# BLL-EBOOK-3506.net
KiCad netlist of a schematic drawn in EAGLE
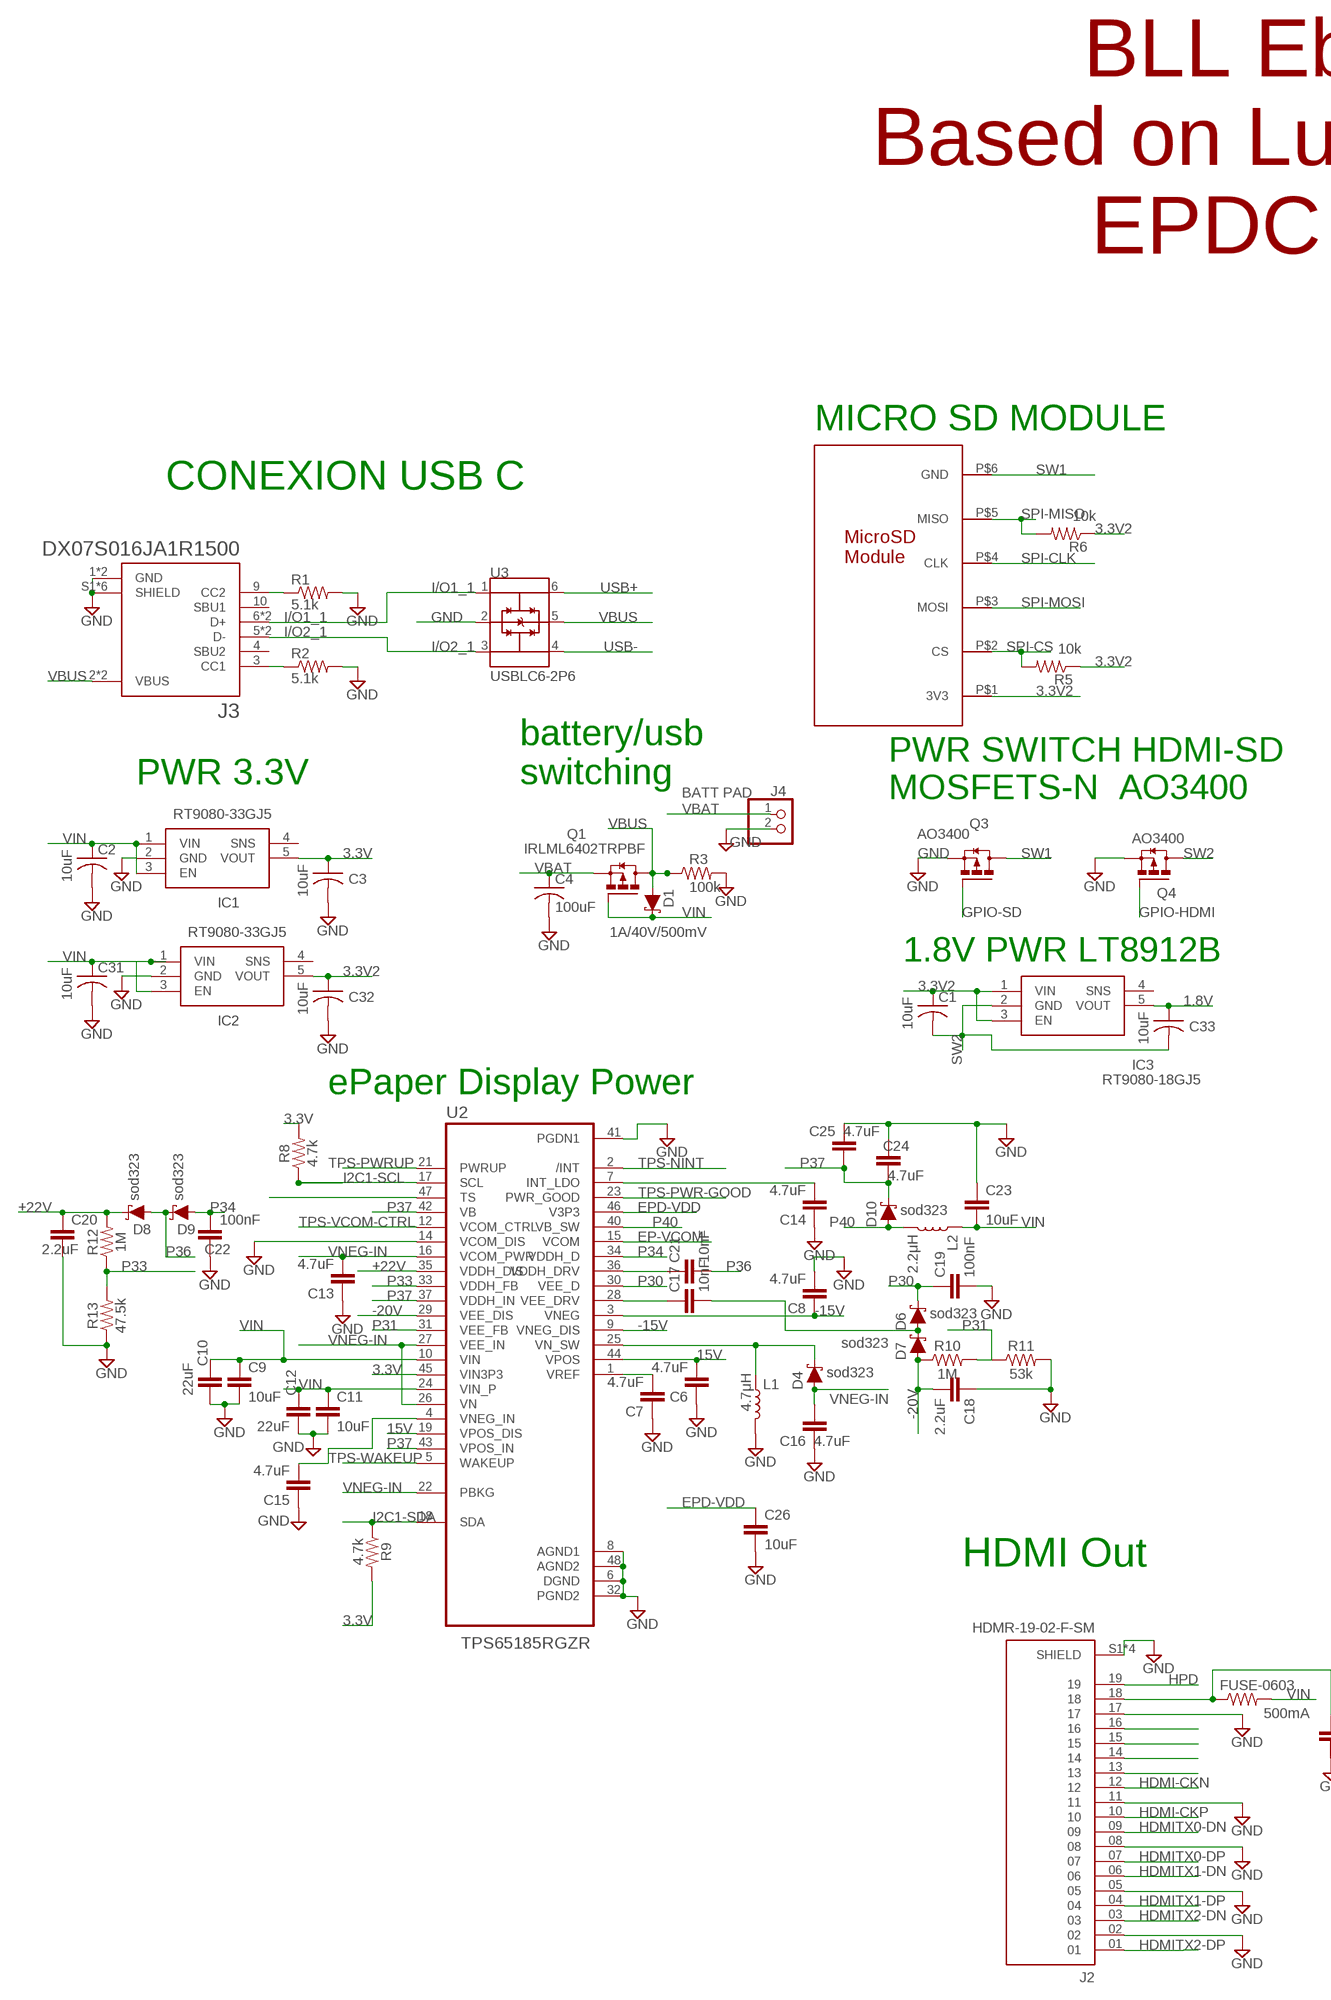
[diagram p0: schematic, sheet 1, part 1 of 2]
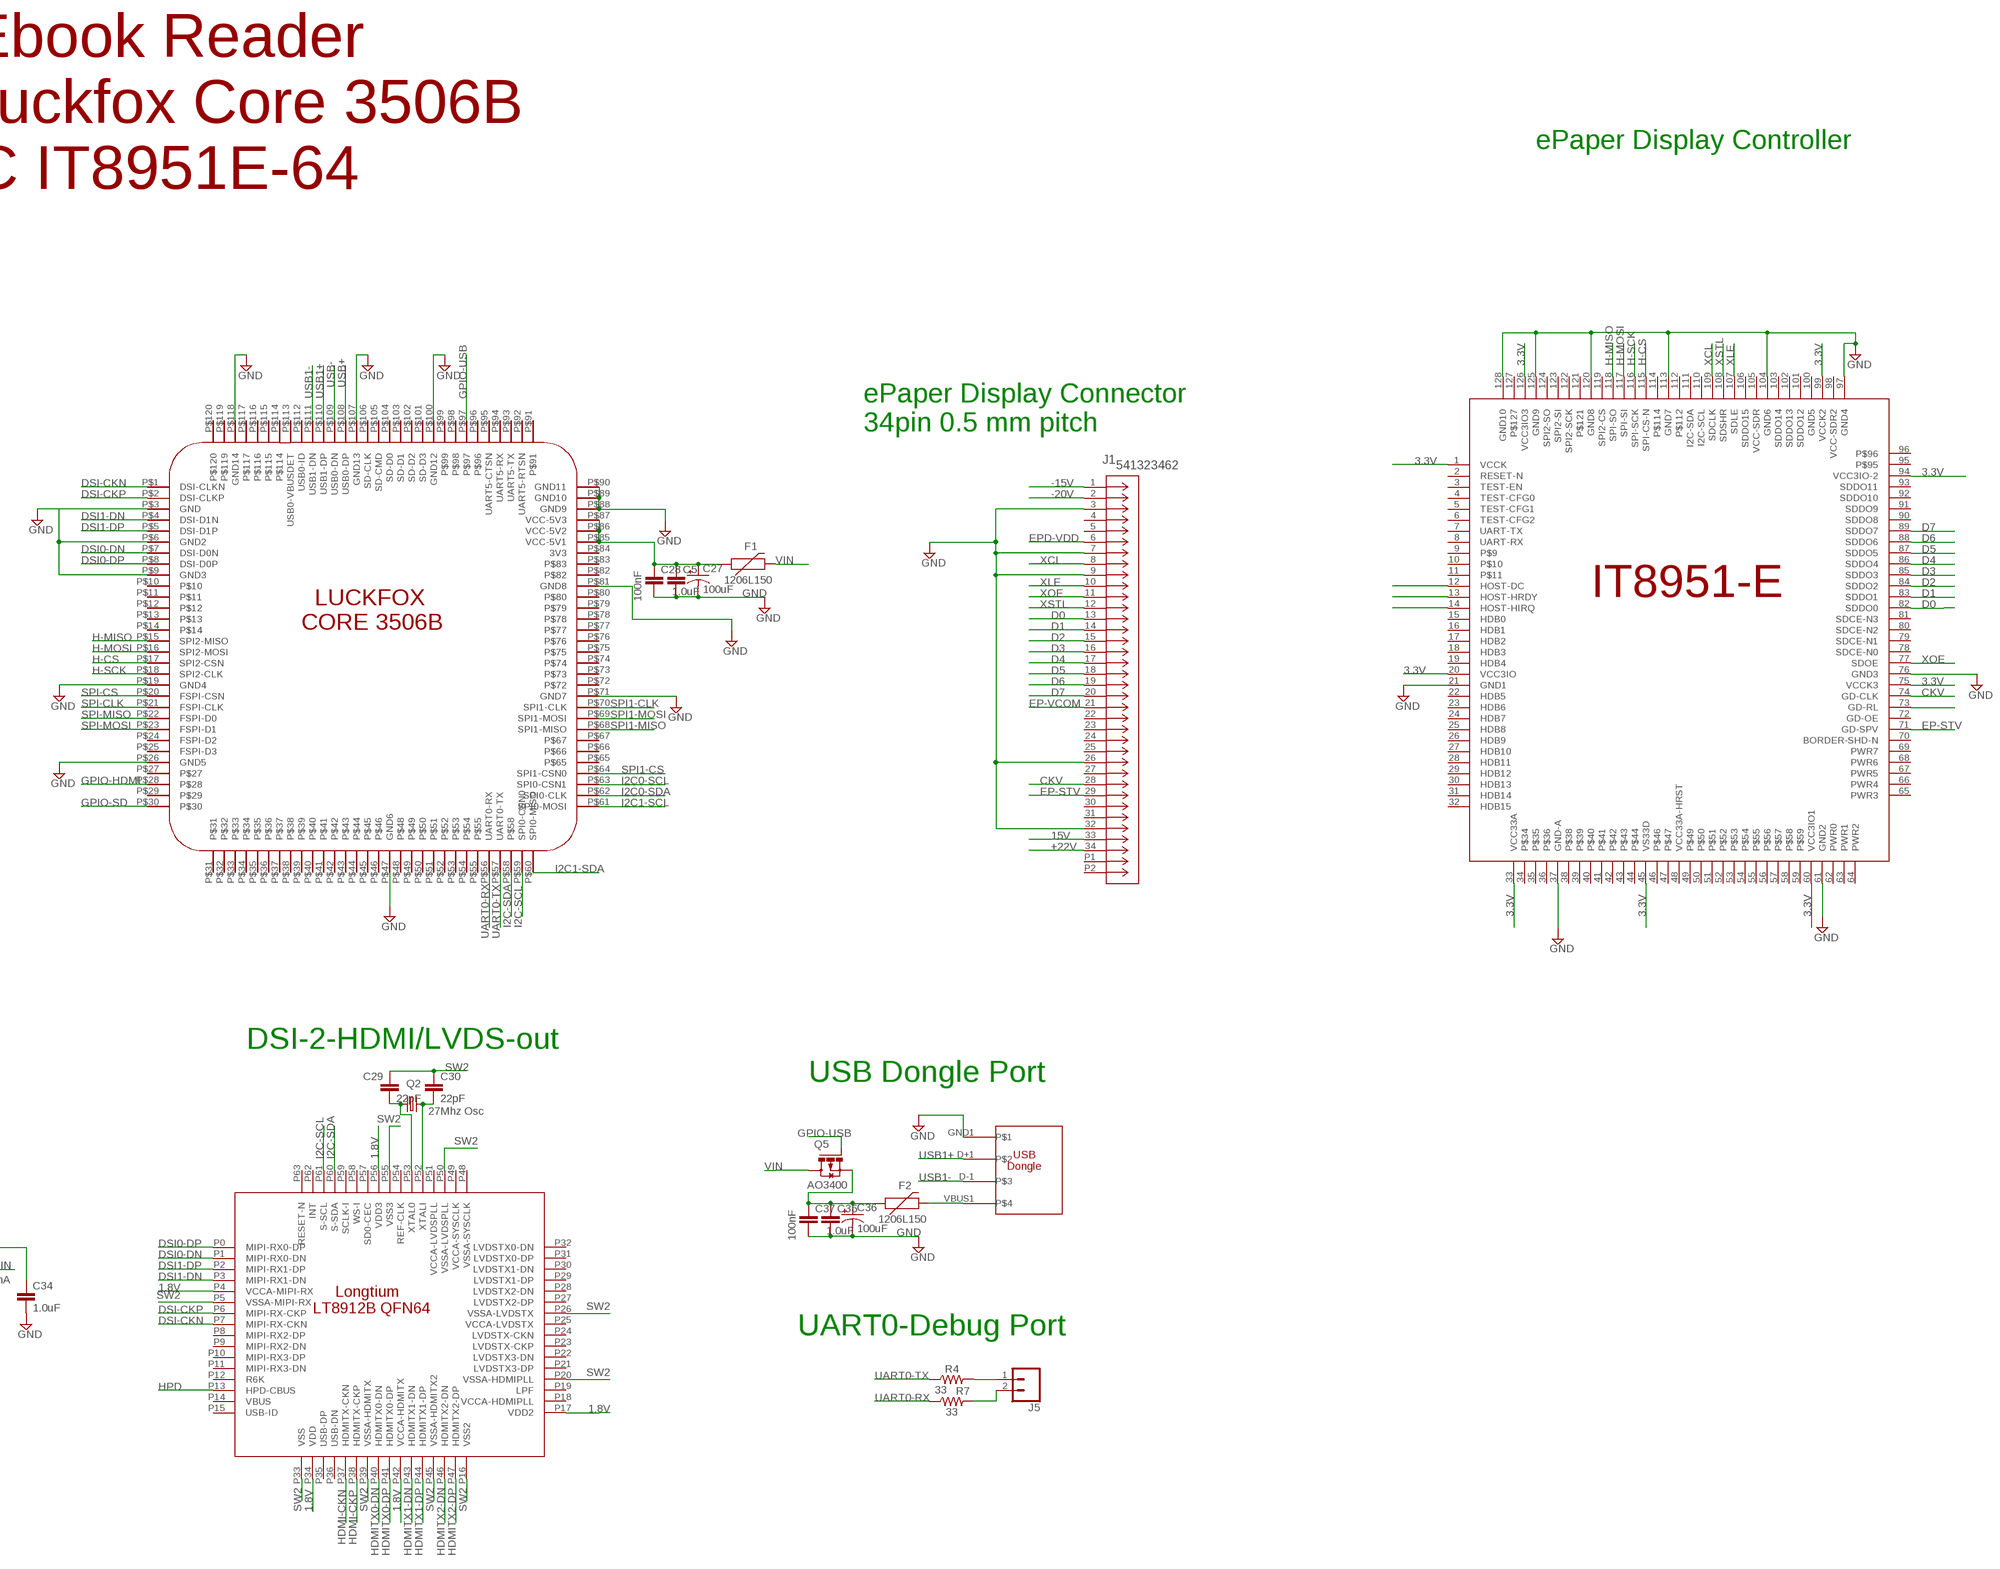
[diagram p1: schematic, sheet 1, part 2 of 2]

(export (version "E")
  (design (tool "Eeschema 10.0.6"))
  (components
    (comp (ref "C1")
      (value "10uF")
      (footprint "eagle-import:C0603")
      (libsource (lib "eagle-import") (part "C-USC0603"))
    )
    (comp (ref "C2")
      (value "10uF")
      (footprint "eagle-import:C0603")
      (libsource (lib "eagle-import") (part "C-USC0603"))
    )
    (comp (ref "C3")
      (value "10uF")
      (footprint "eagle-import:C0603")
      (libsource (lib "eagle-import") (part "C-USC0603"))
    )
    (comp (ref "C4")
      (value "100uF")
      (footprint "eagle-import:C0603")
      (libsource (lib "eagle-import") (part "C-USC0603"))
    )
    (comp (ref "C5")
      (value "1.0uF")
      (footprint "eagle-import:0603")
      (libsource (lib "eagle-import") (part "1.0UF-0603-16V-10%-X7R"))
    )
    (comp (ref "C6")
      (value "4.7uF")
      (footprint "eagle-import:0603")
      (libsource (lib "eagle-import") (part "4.7UF-0603-35V-(20%)"))
    )
    (comp (ref "C7")
      (value "4.7uF")
      (footprint "eagle-import:0603")
      (libsource (lib "eagle-import") (part "4.7UF-0603-35V-(20%)"))
    )
    (comp (ref "C8")
      (value "4.7uF")
      (footprint "eagle-import:0603")
      (libsource (lib "eagle-import") (part "4.7UF-0603-35V-(20%)"))
    )
    (comp (ref "C9")
      (value "10uF")
      (footprint "eagle-import:0805")
      (libsource (lib "eagle-import") (part "10UF-0805-10V-10%"))
    )
    (comp (ref "C10")
      (value "22uF")
      (footprint "eagle-import:0805")
      (libsource (lib "eagle-import") (part "22UF-0805-16V-20%"))
    )
    (comp (ref "C11")
      (value "10uF")
      (footprint "eagle-import:0805")
      (libsource (lib "eagle-import") (part "10UF-0805-10V-10%"))
    )
    (comp (ref "C12")
      (value "22uF")
      (footprint "eagle-import:0805")
      (libsource (lib "eagle-import") (part "22UF-0805-16V-20%"))
    )
    (comp (ref "C13")
      (value "4.7uF")
      (footprint "eagle-import:0603")
      (libsource (lib "eagle-import") (part "4.7UF-0603-35V-(20%)"))
    )
    (comp (ref "C14")
      (value "4.7uF")
      (footprint "eagle-import:0603")
      (libsource (lib "eagle-import") (part "4.7UF-0603-35V-(20%)"))
    )
    (comp (ref "C15")
      (value "4.7uF")
      (footprint "eagle-import:0603")
      (libsource (lib "eagle-import") (part "4.7UF-0603-35V-(20%)"))
    )
    (comp (ref "C16")
      (value "4.7uF")
      (footprint "eagle-import:0603")
      (libsource (lib "eagle-import") (part "4.7UF-0603-35V-(20%)"))
    )
    (comp (ref "C17")
      (value "10nF")
      (footprint "eagle-import:0603")
      (libsource (lib "eagle-import") (part "10NF-0603-50V-10%"))
    )
    (comp (ref "C18")
      (value "2.2uF")
      (footprint "eagle-import:1206")
      (libsource (lib "eagle-import") (part "2.2UF-1206-50V-10%"))
    )
    (comp (ref "C19")
      (value "100nF")
      (footprint "eagle-import:0603")
      (libsource (lib "eagle-import") (part "DNP-0603"))
    )
    (comp (ref "C20")
      (value "2.2uF")
      (footprint "eagle-import:1206")
      (libsource (lib "eagle-import") (part "2.2UF-1206-50V-10%"))
    )
    (comp (ref "C21")
      (value "10nF")
      (footprint "eagle-import:0603")
      (libsource (lib "eagle-import") (part "10NF-0603-50V-10%"))
    )
    (comp (ref "C22")
      (value "100nF")
      (footprint "eagle-import:0603")
      (libsource (lib "eagle-import") (part "DNP-0603"))
    )
    (comp (ref "C23")
      (value "10uF")
      (footprint "eagle-import:0805")
      (libsource (lib "eagle-import") (part "10UF-0805-10V-10%"))
    )
    (comp (ref "C24")
      (value "4.7uF")
      (footprint "eagle-import:0603")
      (libsource (lib "eagle-import") (part "4.7UF-0603-35V-(20%)"))
    )
    (comp (ref "C25")
      (value "4.7uF")
      (footprint "eagle-import:0603")
      (libsource (lib "eagle-import") (part "4.7UF-0603-35V-(20%)"))
    )
    (comp (ref "C26")
      (value "10uF")
      (footprint "eagle-import:0805")
      (libsource (lib "eagle-import") (part "10UF-0805-10V-10%"))
    )
    (comp (ref "C27")
      (value "100uF")
      (footprint "eagle-import:EIA3528")
      (libsource (lib "eagle-import") (part "100UF-POLAR-EIA3528-10V-20%(TANT)"))
    )
    (comp (ref "C28")
      (value "100nF")
      (footprint "eagle-import:0805")
      (libsource (lib "eagle-import") (part "CAP-0805"))
    )
    (comp (ref "C29")
      (value "22pF")
      (footprint "eagle-import:0603")
      (libsource (lib "eagle-import") (part "22PF-0603-50V-5%"))
    )
    (comp (ref "C30")
      (value "22pF")
      (footprint "eagle-import:0603")
      (libsource (lib "eagle-import") (part "22PF-0603-50V-5%"))
    )
    (comp (ref "C31")
      (value "10uF")
      (footprint "eagle-import:C0603")
      (libsource (lib "eagle-import") (part "C-USC0603"))
    )
    (comp (ref "C32")
      (value "10uF")
      (footprint "eagle-import:C0603")
      (libsource (lib "eagle-import") (part "C-USC0603"))
    )
    (comp (ref "C33")
      (value "10uF")
      (footprint "eagle-import:C0603")
      (libsource (lib "eagle-import") (part "C-USC0603"))
    )
    (comp (ref "C34")
      (value "1.0uF")
      (footprint "eagle-import:0603")
      (libsource (lib "eagle-import") (part "1.0UF-0603-16V-10%"))
    )
    (comp (ref "C35")
      (value "1.0uF")
      (footprint "eagle-import:0603")
      (libsource (lib "eagle-import") (part "1.0UF-0603-16V-10%-X7R"))
    )
    (comp (ref "C36")
      (value "100uF")
      (footprint "eagle-import:EIA3528")
      (libsource (lib "eagle-import") (part "100UF-POLAR-EIA3528-10V-20%(TANT)"))
    )
    (comp (ref "C37")
      (value "100nF")
      (footprint "eagle-import:0805")
      (libsource (lib "eagle-import") (part "CAP-0805"))
    )
    (comp (ref "D1")
      (value "1A/40V/500mV")
      (footprint "eagle-import:SMA-DIODE")
      (libsource (lib "eagle-import") (part "DIODE-SCHOTTKY-SS14"))
    )
    (comp (ref "D4")
      (value "sod323")
      (footprint "eagle-import:SOD-323")
      (libsource (lib "eagle-import") (part "DIODE-SCHOTTKY-PMEG4005EJ"))
    )
    (comp (ref "D6")
      (value "sod323")
      (footprint "eagle-import:SOD-323")
      (libsource (lib "eagle-import") (part "DIODE-SCHOTTKY-PMEG4005EJ"))
    )
    (comp (ref "D7")
      (value "sod323")
      (footprint "eagle-import:SOD-323")
      (libsource (lib "eagle-import") (part "DIODE-SCHOTTKY-PMEG4005EJ"))
    )
    (comp (ref "D8")
      (value "sod323")
      (footprint "eagle-import:SOD-323")
      (libsource (lib "eagle-import") (part "DIODE-SCHOTTKY-PMEG4005EJ"))
    )
    (comp (ref "D9")
      (value "sod323")
      (footprint "eagle-import:SOD-323")
      (libsource (lib "eagle-import") (part "DIODE-SCHOTTKY-PMEG4005EJ"))
    )
    (comp (ref "D10")
      (value "sod323")
      (footprint "eagle-import:SOD-323")
      (libsource (lib "eagle-import") (part "DIODE-SCHOTTKY-PMEG4005EJ"))
    )
    (comp (ref "F1")
      (value "1206L150")
      (footprint "eagle-import:1206")
      (libsource (lib "eagle-import") (part "PPTC_6V500MA-2"))
    )
    (comp (ref "F2")
      (value "1206L150")
      (footprint "eagle-import:1206")
      (libsource (lib "eagle-import") (part "PPTC_6V500MA-2"))
    )
    (comp (ref "FUSE-0603")
      (value "500mA")
      (footprint "eagle-import:0603")
      (libsource (lib "eagle-import") (part "1.8MOHM"))
    )
    (comp (ref "IC1")
      (value "RT9080-33GJ5")
      (footprint "eagle-import:SOT94P280X100-5N")
      (fields (field (name "MF") "Richtek USA"))
      (libsource (lib "eagle-import") (part "RT9080-33GJ5"))
    )
    (comp (ref "IC2")
      (value "RT9080-33GJ5")
      (footprint "eagle-import:SOT94P280X100-5N")
      (fields (field (name "MF") "Richtek USA"))
      (libsource (lib "eagle-import") (part "RT9080-33GJ5"))
    )
    (comp (ref "IC3")
      (value "RT9080-18GJ5")
      (footprint "eagle-import:SOT94P280X100-5N")
      (fields (field (name "MF") "Richtek USA") (field (name "MP") "RT9080-33GJ5"))
      (libsource (lib "eagle-import") (part "RT9080-33GJ5"))
    )
    (comp (ref "J1")
      (value "541323462")
      (footprint "eagle-import:CON_541323462_MOL")
      (fields (field (name "MF") "Molex"))
      (libsource (lib "eagle-import") (part "541323462"))
    )
    (comp (ref "J2")
      (value "HDMR-19-02-F-SM")
      (footprint "eagle-import:SAMTEC_HDMR-19-02-F-SM")
      (fields (field (name "MF") "Samtec") (field (name "MP") "HDMR-19-02-F-SM-TR"))
      (libsource (lib "eagle-import") (part "HDMR-19-02-F-SM"))
    )
    (comp (ref "J3")
      (value "DX07S016JA1R1500")
      (footprint "eagle-import:JAE_DX07S016JA1R1500")
      (fields (field (name "MF") "JAE Electronics"))
      (libsource (lib "eagle-import") (part "DX07S016JA1R1500"))
    )
    (comp (ref "J4")
      (value "BATT PAD")
      (footprint "eagle-import:1X02_90")
      (libsource (lib "eagle-import") (part "PINHD-1X2/90"))
    )
    (comp (ref "J5")
      (value "CONN_02LOCK")
      (footprint "eagle-import:1X02_LOCK")
      (libsource (lib "eagle-import") (part "CONN_02LOCK"))
    )
    (comp (ref "L1")
      (value "4.7μH")
      (footprint "eagle-import:1008(2520)")
      (libsource (lib "eagle-import") (part "4.7μH_SHIELDED_INDUCTOR"))
    )
    (comp (ref "L2")
      (value "2.2μH")
      (footprint "eagle-import:0806")
      (libsource (lib "eagle-import") (part "2.2μH_SHIELDED_INDUCTOR"))
    )
    (comp (ref "LT8912")
      (value "LT8912B")
      (footprint "eagle-import:LT8912B")
      (libsource (lib "eagle-import") (part "LT8912B"))
    )
    (comp (ref "Q1")
      (value "IRLML6402TRPBF")
      (footprint "eagle-import:SOT23")
      (fields (field (name "MF") "Infineon Technologies") (field (name "MP") "IRLML6402"))
      (libsource (lib "eagle-import") (part "IRLML6402TRPBF"))
    )
    (comp (ref "Q2")
      (value "27Mhz Osc")
      (footprint "eagle-import:5.0X3.2_2")
      (libsource (lib "eagle-import") (part "KX-9B"))
    )
    (comp (ref "Q3")
      (value "AO3400")
      (footprint "eagle-import:SOT23")
      (fields (field (name "MF") "Infineon Technologies") (field (name "MP") "IRLML6402"))
      (libsource (lib "eagle-import") (part "IRLML6402TRPBF"))
    )
    (comp (ref "Q4")
      (value "AO3400")
      (footprint "eagle-import:SOT23")
      (fields (field (name "MF") "Infineon Technologies") (field (name "MP") "IRLML6402"))
      (libsource (lib "eagle-import") (part "IRLML6402TRPBF"))
    )
    (comp (ref "Q5")
      (value "AO3400")
      (footprint "eagle-import:SOT23")
      (fields (field (name "MF") "Infineon Technologies") (field (name "MP") "IRLML6402"))
      (libsource (lib "eagle-import") (part "IRLML6402TRPBF"))
    )
    (comp (ref "R1")
      (value "5.1k")
      (footprint "eagle-import:M0805")
      (libsource (lib "eagle-import") (part "R-US_M0805"))
    )
    (comp (ref "R2")
      (value "5.1k")
      (footprint "eagle-import:M0805")
      (libsource (lib "eagle-import") (part "R-US_M0805"))
    )
    (comp (ref "R3")
      (value "100k")
      (footprint "eagle-import:R0603")
      (libsource (lib "eagle-import") (part "R-US_R0603"))
    )
    (comp (ref "R4")
      (value "33")
      (footprint "eagle-import:0603")
      (libsource (lib "eagle-import") (part "33OHM-0603-1/10W-1%"))
    )
    (comp (ref "R5")
      (value "10k")
      (footprint "eagle-import:M0805")
      (libsource (lib "eagle-import") (part "R-US_M0805"))
    )
    (comp (ref "R6")
      (value "10k")
      (footprint "eagle-import:M0805")
      (libsource (lib "eagle-import") (part "R-US_M0805"))
    )
    (comp (ref "R7")
      (value "33")
      (footprint "eagle-import:0603")
      (libsource (lib "eagle-import") (part "33OHM-0603-1/10W-1%"))
    )
    (comp (ref "R8")
      (value "4.7k")
      (footprint "eagle-import:0603")
      (libsource (lib "eagle-import") (part "4.7KOHM-0603-1/10W-1%"))
    )
    (comp (ref "R9")
      (value "4.7k")
      (footprint "eagle-import:0603")
      (libsource (lib "eagle-import") (part "4.7KOHM-0603-1/10W-1%"))
    )
    (comp (ref "R10")
      (value "1M")
      (footprint "eagle-import:0603")
      (libsource (lib "eagle-import") (part "1MOHM-0603-1/4W-5%"))
    )
    (comp (ref "R11")
      (value "53k")
      (footprint "eagle-import:0805")
      (libsource (lib "eagle-import") (part "RESISTOR0805"))
    )
    (comp (ref "R12")
      (value "1M")
      (footprint "eagle-import:0603")
      (libsource (lib "eagle-import") (part "1MOHM-0603-1/4W-5%"))
    )
    (comp (ref "R13")
      (value "47.5k")
      (footprint "eagle-import:0805")
      (libsource (lib "eagle-import") (part "RESISTOR0805"))
    )
    (comp (ref "U$1")
      (value "IT8951")
      (footprint "eagle-import:LQFP128_STM")
      (libsource (lib "eagle-import") (part "IT8951"))
    )
    (comp (ref "U$3")
      (value "LUCKFOX_CORE3506")
      (footprint "eagle-import:CORE3506")
      (libsource (lib "eagle-import") (part "LUCKFOX_CORE3506"))
    )
    (comp (ref "U$4")
      (value "MICROSD-MODULE")
      (footprint "eagle-import:MICROSD-MOD")
      (libsource (lib "eagle-import") (part "MICROSD-MODULE"))
    )
    (comp (ref "U$5")
      (value "USB-WIFI-DONGLE")
      (footprint "eagle-import:USB-A-SMT-MALE")
      (libsource (lib "eagle-import") (part "USB-WIFI-DONGLE"))
    )
    (comp (ref "U2")
      (value "TPS65185RGZR")
      (footprint "eagle-import:QFN50P700X700X100-49N")
      (fields (field (name "MF") "Texas Instruments"))
      (libsource (lib "eagle-import") (part "TPS65185RGZR"))
    )
    (comp (ref "U3")
      (value "USBLC6-2P6")
      (footprint "eagle-import:SOT50P160X60-6N")
      (fields (field (name "MF") "STMicroelectronics"))
      (libsource (lib "eagle-import") (part "USBLC6-2P6"))
    )
  )
  (nets
    (net (code "1") (name "/+22V") (class "Default")
      (node (ref "C20") (pin "1") (pinfunction "1_1") (pintype "passive"))
      (node (ref "D8") (pin "C") (pinfunction "C_C") (pintype "passive"))
      (node (ref "J1") (pin "34") (pinfunction "34_34") (pintype "passive"))
      (node (ref "R12") (pin "2") (pinfunction "2_2") (pintype "passive"))
      (node (ref "U2") (pin "35") (pinfunction "VDDH_DIS_35") (pintype "input"))
    )
    (net (code "2") (name "/-15V") (class "Default")
      (node (ref "C8") (pin "1") (pinfunction "1_1") (pintype "passive"))
      (node (ref "J1") (pin "1") (pinfunction "1_1") (pintype "passive"))
      (node (ref "U2") (pin "3") (pinfunction "VNEG_3") (pintype "output"))
      (node (ref "U2") (pin "9") (pinfunction "VNEG_DIS_9") (pintype "output"))
    )
    (net (code "3") (name "/-20V") (class "Default")
      (node (ref "C18") (pin "2") (pinfunction "2_2") (pintype "passive"))
      (node (ref "D7") (pin "A") (pinfunction "A_A") (pintype "passive"))
      (node (ref "J1") (pin "2") (pinfunction "2_2") (pintype "passive"))
      (node (ref "R10") (pin "1") (pinfunction "1_1") (pintype "passive"))
      (node (ref "U2") (pin "29") (pinfunction "VEE_DIS_29") (pintype "input"))
    )
    (net (code "4") (name "/1.8V") (class "Default")
      (node (ref "C33") (pin "1") (pinfunction "1_1") (pintype "passive"))
      (node (ref "IC3") (pin "5") (pinfunction "VOUT_5") (pintype "bidirectional"))
      (node (ref "LT8912") (pin "P17") (pinfunction "VDD2_P17") (pintype "bidirectional"))
      (node (ref "LT8912") (pin "P34") (pinfunction "VDD_P34") (pintype "bidirectional"))
      (node (ref "LT8912") (pin "P4") (pinfunction "VCCA-MIPI-RX_P4") (pintype "bidirectional"))
      (node (ref "LT8912") (pin "P42") (pinfunction "VCCA-HDMITX_P42") (pintype "bidirectional"))
      (node (ref "LT8912") (pin "P56") (pinfunction "VDD3_P56") (pintype "bidirectional"))
    )
    (net (code "5") (name "/3.3V") (class "Default")
      (node (ref "C3") (pin "1") (pinfunction "1_1") (pintype "passive"))
      (node (ref "IC1") (pin "5") (pinfunction "VOUT_5") (pintype "bidirectional"))
      (node (ref "R8") (pin "2") (pinfunction "2_2") (pintype "passive"))
      (node (ref "R9") (pin "2") (pinfunction "2_2") (pintype "passive"))
      (node (ref "U$1") (pin "1") (pinfunction "VCCK_1") (pintype "bidirectional"))
      (node (ref "U$1") (pin "126") (pinfunction "VCC3IO3_126") (pintype "bidirectional"))
      (node (ref "U$1") (pin "20") (pinfunction "VCC3IO_20") (pintype "bidirectional"))
      (node (ref "U$1") (pin "33") (pinfunction "VCC33A_33") (pintype "bidirectional"))
      (node (ref "U$1") (pin "45") (pinfunction "VS33D_45") (pintype "bidirectional"))
      (node (ref "U$1") (pin "60") (pinfunction "VCC3IO1_60") (pintype "bidirectional"))
      (node (ref "U$1") (pin "75") (pinfunction "VCCK3_75") (pintype "bidirectional"))
      (node (ref "U$1") (pin "94") (pinfunction "VCC3IO-2_94") (pintype "bidirectional"))
      (node (ref "U$1") (pin "99") (pinfunction "VCCK2_99") (pintype "bidirectional"))
      (node (ref "U2") (pin "45") (pinfunction "VIN3P3_45") (pintype "input"))
    )
    (net (code "6") (name "/3.3V2") (class "Default")
      (node (ref "C1") (pin "1") (pinfunction "1_1") (pintype "passive"))
      (node (ref "C32") (pin "1") (pinfunction "1_1") (pintype "passive"))
      (node (ref "IC2") (pin "5") (pinfunction "VOUT_5") (pintype "bidirectional"))
      (node (ref "IC3") (pin "1") (pinfunction "VIN_1") (pintype "bidirectional"))
      (node (ref "IC3") (pin "3") (pinfunction "EN_3") (pintype "bidirectional"))
      (node (ref "R5") (pin "1") (pinfunction "1_1") (pintype "passive"))
      (node (ref "R6") (pin "1") (pinfunction "1_1") (pintype "passive"))
      (node (ref "U$4") (pin "P$1") (pinfunction "3V3_P$1") (pintype "bidirectional"))
    )
    (net (code "7") (name "/15V") (class "Default")
      (node (ref "C6") (pin "2") (pinfunction "2_2") (pintype "passive"))
      (node (ref "J1") (pin "33") (pinfunction "33_33") (pintype "passive"))
      (node (ref "U2") (pin "19") (pinfunction "VPOS_DIS_19") (pintype "input"))
      (node (ref "U2") (pin "44") (pinfunction "VPOS_44") (pintype "output"))
    )
    (net (code "8") (name "/CKV") (class "Default")
      (node (ref "J1") (pin "28") (pinfunction "28_28") (pintype "passive"))
      (node (ref "U$1") (pin "74") (pinfunction "GD-CLK_74") (pintype "bidirectional"))
    )
    (net (code "9") (name "/D0") (class "Default")
      (node (ref "J1") (pin "13") (pinfunction "13_13") (pintype "passive"))
      (node (ref "U$1") (pin "82") (pinfunction "SDDO0_82") (pintype "bidirectional"))
    )
    (net (code "10") (name "/D1") (class "Default")
      (node (ref "J1") (pin "14") (pinfunction "14_14") (pintype "passive"))
      (node (ref "U$1") (pin "83") (pinfunction "SDDO1_83") (pintype "bidirectional"))
    )
    (net (code "11") (name "/D2") (class "Default")
      (node (ref "J1") (pin "15") (pinfunction "15_15") (pintype "passive"))
      (node (ref "U$1") (pin "84") (pinfunction "SDDO2_84") (pintype "bidirectional"))
    )
    (net (code "12") (name "/D3") (class "Default")
      (node (ref "J1") (pin "16") (pinfunction "16_16") (pintype "passive"))
      (node (ref "U$1") (pin "85") (pinfunction "SDDO3_85") (pintype "bidirectional"))
    )
    (net (code "13") (name "/D4") (class "Default")
      (node (ref "J1") (pin "17") (pinfunction "17_17") (pintype "passive"))
      (node (ref "U$1") (pin "86") (pinfunction "SDDO4_86") (pintype "bidirectional"))
    )
    (net (code "14") (name "/D5") (class "Default")
      (node (ref "J1") (pin "18") (pinfunction "18_18") (pintype "passive"))
      (node (ref "U$1") (pin "87") (pinfunction "SDDO5_87") (pintype "bidirectional"))
    )
    (net (code "15") (name "/D6") (class "Default")
      (node (ref "J1") (pin "19") (pinfunction "19_19") (pintype "passive"))
      (node (ref "U$1") (pin "88") (pinfunction "SDDO6_88") (pintype "bidirectional"))
    )
    (net (code "16") (name "/D7") (class "Default")
      (node (ref "J1") (pin "20") (pinfunction "20_20") (pintype "passive"))
      (node (ref "U$1") (pin "89") (pinfunction "SDDO7_89") (pintype "bidirectional"))
    )
    (net (code "17") (name "/DSI-CKN") (class "Default")
      (node (ref "LT8912") (pin "P7") (pinfunction "MIPI-RX-CKN_P7") (pintype "bidirectional"))
      (node (ref "U$3") (pin "P$1") (pinfunction "DSI-CLKN_P$1") (pintype "output"))
    )
    (net (code "18") (name "/DSI-CKP") (class "Default")
      (node (ref "LT8912") (pin "P6") (pinfunction "MIPI-RX-CKP_P6") (pintype "bidirectional"))
      (node (ref "U$3") (pin "P$2") (pinfunction "DSI-CLKP_P$2") (pintype "bidirectional"))
    )
    (net (code "19") (name "/DSI0-DN") (class "Default")
      (node (ref "LT8912") (pin "P1") (pinfunction "MIPI-RX0-DN_P1") (pintype "bidirectional"))
      (node (ref "U$3") (pin "P$7") (pinfunction "DSI-D0N_P$7") (pintype "bidirectional"))
    )
    (net (code "20") (name "/DSI0-DP") (class "Default")
      (node (ref "LT8912") (pin "P0") (pinfunction "MIPI-RX0-DP_P0") (pintype "bidirectional"))
      (node (ref "U$3") (pin "P$8") (pinfunction "DSI-D0P_P$8") (pintype "bidirectional"))
    )
    (net (code "21") (name "/DSI1-DN") (class "Default")
      (node (ref "LT8912") (pin "P3") (pinfunction "MIPI-RX1-DN_P3") (pintype "bidirectional"))
      (node (ref "U$3") (pin "P$4") (pinfunction "DSI-D1N_P$4") (pintype "bidirectional"))
    )
    (net (code "22") (name "/DSI1-DP") (class "Default")
      (node (ref "LT8912") (pin "P2") (pinfunction "MIPI-RX1-DP_P2") (pintype "bidirectional"))
      (node (ref "U$3") (pin "P$5") (pinfunction "DSI-D1P_P$5") (pintype "bidirectional"))
    )
    (net (code "23") (name "/EP-STV") (class "Default")
      (node (ref "J1") (pin "29") (pinfunction "29_29") (pintype "passive"))
      (node (ref "U$1") (pin "71") (pinfunction "GD-SPV_71") (pintype "bidirectional"))
    )
    (net (code "24") (name "/EP-VCOM") (class "Default")
      (node (ref "J1") (pin "21") (pinfunction "21_21") (pintype "passive"))
      (node (ref "U2") (pin "15") (pinfunction "VCOM_15") (pintype "output"))
    )
    (net (code "25") (name "/EPD-VDD") (class "Default")
      (node (ref "C26") (pin "1") (pinfunction "1_1") (pintype "passive"))
      (node (ref "J1") (pin "6") (pinfunction "6_6") (pintype "passive"))
      (node (ref "U2") (pin "46") (pinfunction "V3P3_46") (pintype "output"))
    )
    (net (code "26") (name "/GPIO-HDMI") (class "Default")
      (node (ref "Q4") (pin "1") (pinfunction "G_1") (pintype "passive"))
      (node (ref "U$3") (pin "P$28") (pinfunction "P$28_P$28") (pintype "bidirectional"))
    )
    (net (code "27") (name "/GPIO-SD") (class "Default")
      (node (ref "Q3") (pin "1") (pinfunction "G_1") (pintype "passive"))
      (node (ref "U$3") (pin "P$30") (pinfunction "P$30_P$30") (pintype "bidirectional"))
    )
    (net (code "28") (name "/GPIO-USB") (class "Default")
      (node (ref "Q5") (pin "1") (pinfunction "G_1") (pintype "passive"))
      (node (ref "U$3") (pin "P$97") (pinfunction "P$97_P$97") (pintype "bidirectional"))
    )
    (net (code "29") (name "/H-CS") (class "Default")
      (node (ref "U$1") (pin "115") (pinfunction "SPI-CS-N_115") (pintype "bidirectional"))
      (node (ref "U$3") (pin "P$17") (pinfunction "SPI2-CSN_P$17") (pintype "bidirectional"))
    )
    (net (code "30") (name "/H-MISO") (class "Default")
      (node (ref "U$1") (pin "118") (pinfunction "SPI-SO_118") (pintype "bidirectional"))
      (node (ref "U$3") (pin "P$15") (pinfunction "SPI2-MISO_P$15") (pintype "bidirectional"))
    )
    (net (code "31") (name "/H-MOSI") (class "Default")
      (node (ref "U$1") (pin "117") (pinfunction "SPI-SI_117") (pintype "bidirectional"))
      (node (ref "U$3") (pin "P$16") (pinfunction "SPI2-MOSI_P$16") (pintype "bidirectional"))
    )
    (net (code "32") (name "/H-SCK") (class "Default")
      (node (ref "U$1") (pin "116") (pinfunction "SPI-SCK_116") (pintype "bidirectional"))
      (node (ref "U$3") (pin "P$18") (pinfunction "SPI2-CLK_P$18") (pintype "bidirectional"))
    )
    (net (code "33") (name "/HDMI-CKN") (class "Default")
      (node (ref "J2") (pin "12") (pinfunction "12_12") (pintype "bidirectional"))
      (node (ref "LT8912") (pin "P37") (pinfunction "HDMITX-CKN_P37") (pintype "bidirectional"))
    )
    (net (code "34") (name "/HDMI-CKP") (class "Default")
      (node (ref "J2") (pin "10") (pinfunction "10_10") (pintype "bidirectional"))
      (node (ref "LT8912") (pin "P38") (pinfunction "HDMITX-CKP_P38") (pintype "bidirectional"))
    )
    (net (code "35") (name "/HDMITX0-DN") (class "Default")
      (node (ref "J2") (pin "09") (pinfunction "09_09") (pintype "bidirectional"))
      (node (ref "LT8912") (pin "P40") (pinfunction "HDMITX0-DN_P40") (pintype "bidirectional"))
    )
    (net (code "36") (name "/HDMITX0-DP") (class "Default")
      (node (ref "J2") (pin "07") (pinfunction "07_07") (pintype "bidirectional"))
      (node (ref "LT8912") (pin "P41") (pinfunction "HDMITX0-DP_P41") (pintype "bidirectional"))
    )
    (net (code "37") (name "/HDMITX1-DN") (class "Default")
      (node (ref "J2") (pin "06") (pinfunction "06_06") (pintype "bidirectional"))
      (node (ref "LT8912") (pin "P43") (pinfunction "HDMITX1-DN_P43") (pintype "bidirectional"))
    )
    (net (code "38") (name "/HDMITX1-DP") (class "Default")
      (node (ref "J2") (pin "04") (pinfunction "04_04") (pintype "bidirectional"))
      (node (ref "LT8912") (pin "P44") (pinfunction "HDMITX1-DP_P44") (pintype "bidirectional"))
    )
    (net (code "39") (name "/HDMITX2-DN") (class "Default")
      (node (ref "J2") (pin "03") (pinfunction "03_03") (pintype "bidirectional"))
      (node (ref "LT8912") (pin "P46") (pinfunction "HDMITX2-DN_P46") (pintype "bidirectional"))
    )
    (net (code "40") (name "/HDMITX2-DP") (class "Default")
      (node (ref "J2") (pin "01") (pinfunction "01_01") (pintype "bidirectional"))
      (node (ref "LT8912") (pin "P47") (pinfunction "HDMITX2-DP_P47") (pintype "bidirectional"))
    )
    (net (code "41") (name "/HPD") (class "Default")
      (node (ref "J2") (pin "19") (pinfunction "19_19") (pintype "bidirectional"))
      (node (ref "LT8912") (pin "P13") (pinfunction "HPD-CBUS_P13") (pintype "bidirectional"))
    )
    (net (code "42") (name "/I2C-SCL") (class "Default")
      (node (ref "LT8912") (pin "P61") (pinfunction "S-SCL_P61") (pintype "bidirectional"))
      (node (ref "U$3") (pin "P$59") (pinfunction "SPI0-CSN0_P$59") (pintype "bidirectional"))
    )
    (net (code "43") (name "/I2C-SDA") (class "Default")
      (node (ref "LT8912") (pin "P60") (pinfunction "S-SDA_P60") (pintype "bidirectional"))
      (node (ref "U$3") (pin "P$58") (pinfunction "P$58_P$58") (pintype "bidirectional"))
    )
    (net (code "44") (name "/I2C0-SCL") (class "Default")
      (node (ref "U$3") (pin "P$63") (pinfunction "SPI0-CSN1_P$63") (pintype "bidirectional"))
    )
    (net (code "45") (name "/I2C0-SDA") (class "Default")
      (node (ref "U$3") (pin "P$62") (pinfunction "SPI0-CLK_P$62") (pintype "bidirectional"))
    )
    (net (code "46") (name "/I2C1-SCL") (class "Default")
      (node (ref "R8") (pin "1") (pinfunction "1_1") (pintype "passive"))
      (node (ref "U$3") (pin "P$61") (pinfunction "SPI0-MOSI_P$61") (pintype "bidirectional"))
      (node (ref "U2") (pin "17") (pinfunction "SCL_17") (pintype "input"))
    )
    (net (code "47") (name "/I2C1-SDA") (class "Default")
      (node (ref "R9") (pin "1") (pinfunction "1_1") (pintype "passive"))
      (node (ref "U$3") (pin "P$60") (pinfunction "SPI0-MISO_P$60") (pintype "bidirectional"))
      (node (ref "U2") (pin "18") (pinfunction "SDA_18") (pintype "bidirectional"))
    )
    (net (code "48") (name "/I{slash}O1_1") (class "Default")
      (node (ref "J3") (pin "6") (pinfunction "D+_6") (pintype "passive"))
      (node (ref "J3") (pin "7") (pinfunction "D+_7") (pintype "passive"))
      (node (ref "U3") (pin "1") (pinfunction "I/O1_1_1") (pintype "bidirectional"))
    )
    (net (code "49") (name "/I{slash}O2_1") (class "Default")
      (node (ref "J3") (pin "5") (pinfunction "D-_5") (pintype "passive"))
      (node (ref "J3") (pin "8") (pinfunction "D-_8") (pintype "passive"))
      (node (ref "U3") (pin "3") (pinfunction "I/O2_1_3") (pintype "bidirectional"))
    )
    (net (code "50") (name "/P30") (class "Default")
      (node (ref "C19") (pin "1") (pinfunction "1_1") (pintype "passive"))
      (node (ref "D6") (pin "C") (pinfunction "C_C") (pintype "passive"))
      (node (ref "U2") (pin "30") (pinfunction "VEE_D_30") (pintype "output"))
    )
    (net (code "51") (name "/P31") (class "Default")
      (node (ref "R10") (pin "2") (pinfunction "2_2") (pintype "passive"))
      (node (ref "R11") (pin "1") (pinfunction "1_1") (pintype "passive"))
      (node (ref "U2") (pin "31") (pinfunction "VEE_FB_31") (pintype "input"))
    )
    (net (code "52") (name "/P33") (class "Default")
      (node (ref "R12") (pin "1") (pinfunction "1_1") (pintype "passive"))
      (node (ref "R13") (pin "2") (pinfunction "2_2") (pintype "passive"))
      (node (ref "U2") (pin "33") (pinfunction "VDDH_FB_33") (pintype "input"))
    )
    (net (code "53") (name "/P34") (class "Default")
      (node (ref "C22") (pin "2") (pinfunction "2_2") (pintype "passive"))
      (node (ref "D9") (pin "A") (pinfunction "A_A") (pintype "passive"))
      (node (ref "U2") (pin "34") (pinfunction "VDDH_D_34") (pintype "output"))
    )
    (net (code "54") (name "/P36") (class "Default")
      (node (ref "C21") (pin "2") (pinfunction "2_2") (pintype "passive"))
      (node (ref "D8") (pin "A") (pinfunction "A_A") (pintype "passive"))
      (node (ref "D9") (pin "C") (pinfunction "C_C") (pintype "passive"))
    )
    (net (code "55") (name "/P37") (class "Default")
      (node (ref "C24") (pin "1") (pinfunction "1_1") (pintype "passive"))
      (node (ref "C25") (pin "1") (pinfunction "1_1") (pintype "passive"))
      (node (ref "D10") (pin "C") (pinfunction "C_C") (pintype "passive"))
      (node (ref "U2") (pin "37") (pinfunction "VDDH_IN_37") (pintype "input"))
      (node (ref "U2") (pin "42") (pinfunction "VB_42") (pintype "input"))
      (node (ref "U2") (pin "43") (pinfunction "VPOS_IN_43") (pintype "input"))
    )
    (net (code "56") (name "/P40") (class "Default")
      (node (ref "D10") (pin "A") (pinfunction "A_A") (pintype "passive"))
      (node (ref "L2") (pin "2") (pinfunction "2_2") (pintype "passive"))
      (node (ref "U2") (pin "40") (pinfunction "VB_SW_40") (pintype "output"))
    )
    (net (code "57") (name "/SPI-CLK") (class "Default")
      (node (ref "U$3") (pin "P$21") (pinfunction "FSPI-CLK_P$21") (pintype "bidirectional"))
      (node (ref "U$4") (pin "P$4") (pinfunction "CLK_P$4") (pintype "bidirectional"))
    )
    (net (code "58") (name "/SPI-CS") (class "Default")
      (node (ref "R5") (pin "2") (pinfunction "2_2") (pintype "passive"))
      (node (ref "U$3") (pin "P$20") (pinfunction "FSPI-CSN_P$20") (pintype "bidirectional"))
      (node (ref "U$4") (pin "P$2") (pinfunction "CS_P$2") (pintype "bidirectional"))
    )
    (net (code "59") (name "/SPI-MISO") (class "Default")
      (node (ref "R6") (pin "2") (pinfunction "2_2") (pintype "passive"))
      (node (ref "U$3") (pin "P$22") (pinfunction "FSPI-D0_P$22") (pintype "bidirectional"))
      (node (ref "U$4") (pin "P$5") (pinfunction "MISO_P$5") (pintype "bidirectional"))
    )
    (net (code "60") (name "/SPI-MOSI") (class "Default")
      (node (ref "U$3") (pin "P$23") (pinfunction "FSPI-D1_P$23") (pintype "bidirectional"))
      (node (ref "U$4") (pin "P$3") (pinfunction "MOSI_P$3") (pintype "bidirectional"))
    )
    (net (code "61") (name "/SPI1-CLK") (class "Default")
      (node (ref "U$3") (pin "P$70") (pinfunction "SPI1-CLK_P$70") (pintype "bidirectional"))
    )
    (net (code "62") (name "/SPI1-CS") (class "Default")
      (node (ref "U$3") (pin "P$64") (pinfunction "SPI1-CSN0_P$64") (pintype "bidirectional"))
    )
    (net (code "63") (name "/SPI1-MISO") (class "Default")
      (node (ref "U$3") (pin "P$68") (pinfunction "SPI1-MISO_P$68") (pintype "bidirectional"))
    )
    (net (code "64") (name "/SPI1-MOSI") (class "Default")
      (node (ref "U$3") (pin "P$69") (pinfunction "SPI1-MOSI_P$69") (pintype "bidirectional"))
    )
    (net (code "65") (name "/SW1") (class "Default")
      (node (ref "Q3") (pin "3") (pinfunction "D_3") (pintype "passive"))
      (node (ref "U$4") (pin "P$6") (pinfunction "GND_P$6") (pintype "bidirectional"))
    )
    (net (code "66") (name "/SW2") (class "Default")
      (node (ref "C1") (pin "2") (pinfunction "2_2") (pintype "passive"))
      (node (ref "C29") (pin "1") (pinfunction "1_1") (pintype "passive"))
      (node (ref "C30") (pin "1") (pinfunction "1_1") (pintype "passive"))
      (node (ref "C33") (pin "2") (pinfunction "2_2") (pintype "passive"))
      (node (ref "IC3") (pin "2") (pinfunction "GND_2") (pintype "bidirectional"))
      (node (ref "LT8912") (pin "P16") (pinfunction "VSS2_P16") (pintype "bidirectional"))
      (node (ref "LT8912") (pin "P20") (pinfunction "VSSA-HDMIPLL_P20") (pintype "bidirectional"))
      (node (ref "LT8912") (pin "P26") (pinfunction "VSSA-LVDSTX_P26") (pintype "bidirectional"))
      (node (ref "LT8912") (pin "P33") (pinfunction "VSS_P33") (pintype "bidirectional"))
      (node (ref "LT8912") (pin "P39") (pinfunction "VSSA-HDMITX_P39") (pintype "bidirectional"))
      (node (ref "LT8912") (pin "P45") (pinfunction "VSSA-HDMITX2_P45") (pintype "bidirectional"))
      (node (ref "LT8912") (pin "P5") (pinfunction "VSSA-MIPI-RX_P5") (pintype "bidirectional"))
      (node (ref "LT8912") (pin "P50") (pinfunction "VSSA-LVDSPLL_P50") (pintype "bidirectional"))
      (node (ref "LT8912") (pin "P55") (pinfunction "VSS3_P55") (pintype "bidirectional"))
      (node (ref "Q4") (pin "3") (pinfunction "D_3") (pintype "passive"))
    )
    (net (code "67") (name "/TPS-NINT") (class "Default")
      (node (ref "U2") (pin "2") (pinfunction "/INT_2") (pintype "output"))
    )
    (net (code "68") (name "/TPS-PWR-GOOD") (class "Default")
      (node (ref "U2") (pin "23") (pinfunction "PWR_GOOD_23") (pintype "output"))
    )
    (net (code "69") (name "/TPS-PWRUP") (class "Default")
      (node (ref "U2") (pin "21") (pinfunction "PWRUP_21") (pintype "input"))
    )
    (net (code "70") (name "/TPS-VCOM-CTRL") (class "Default")
      (node (ref "U2") (pin "12") (pinfunction "VCOM_CTRL_12") (pintype "input"))
    )
    (net (code "71") (name "/TPS-WAKEUP") (class "Default")
      (node (ref "U2") (pin "5") (pinfunction "WAKEUP_5") (pintype "input"))
    )
    (net (code "72") (name "/UART0-RX") (class "Default")
      (node (ref "R7") (pin "1") (pinfunction "1_1") (pintype "passive"))
      (node (ref "U$3") (pin "P$56") (pinfunction "UART0-RX_P$56") (pintype "bidirectional"))
    )
    (net (code "73") (name "/UART0-TX") (class "Default")
      (node (ref "R4") (pin "1") (pinfunction "1_1") (pintype "passive"))
      (node (ref "U$3") (pin "P$57") (pinfunction "UART0-TX_P$57") (pintype "bidirectional"))
    )
    (net (code "74") (name "/USB+") (class "Default")
      (node (ref "U$3") (pin "P$108") (pinfunction "USB0-DP_P$108") (pintype "bidirectional"))
      (node (ref "U3") (pin "6") (pinfunction "I/O1_2_6") (pintype "bidirectional"))
    )
    (net (code "75") (name "/USB-") (class "Default")
      (node (ref "U$3") (pin "P$109") (pinfunction "USB0-DN_P$109") (pintype "bidirectional"))
      (node (ref "U3") (pin "4") (pinfunction "I/O2_2_4") (pintype "bidirectional"))
    )
    (net (code "76") (name "/USB1+") (class "Default")
      (node (ref "U$3") (pin "P$110") (pinfunction "USB1-DP_P$110") (pintype "bidirectional"))
      (node (ref "U$5") (pin "D+1") (pinfunction "P$2_D+1") (pintype "bidirectional"))
    )
    (net (code "77") (name "/USB1-") (class "Default")
      (node (ref "U$3") (pin "P$111") (pinfunction "USB1-DN_P$111") (pintype "bidirectional"))
      (node (ref "U$5") (pin "D-1") (pinfunction "P$3_D-1") (pintype "bidirectional"))
    )
    (net (code "78") (name "/VBAT") (class "Default")
      (node (ref "C4") (pin "1") (pinfunction "1_1") (pintype "passive"))
      (node (ref "J4") (pin "1") (pinfunction "1_1") (pintype "passive"))
      (node (ref "Q1") (pin "2") (pinfunction "S_2") (pintype "passive"))
    )
    (net (code "79") (name "/VBUS") (class "Default")
      (node (ref "D1") (pin "A") (pinfunction "A_A") (pintype "passive"))
      (node (ref "J3") (pin "11") (pinfunction "VBUS_11") (pintype "power_in"))
      (node (ref "J3") (pin "2") (pinfunction "VBUS_2") (pintype "power_in"))
      (node (ref "Q1") (pin "3") (pinfunction "D_3") (pintype "passive"))
      (node (ref "R3") (pin "1") (pinfunction "1_1") (pintype "passive"))
      (node (ref "U3") (pin "5") (pinfunction "VBUS_5") (pintype "power_in"))
    )
    (net (code "80") (name "/VIN") (class "Default")
      (node (ref "C10") (pin "1") (pinfunction "1_1") (pintype "passive"))
      (node (ref "C11") (pin "1") (pinfunction "1_1") (pintype "passive"))
      (node (ref "C12") (pin "1") (pinfunction "1_1") (pintype "passive"))
      (node (ref "C2") (pin "1") (pinfunction "1_1") (pintype "passive"))
      (node (ref "C23") (pin "2") (pinfunction "2_2") (pintype "passive"))
      (node (ref "C31") (pin "1") (pinfunction "1_1") (pintype "passive"))
      (node (ref "C9") (pin "1") (pinfunction "1_1") (pintype "passive"))
      (node (ref "D1") (pin "C") (pinfunction "C_C") (pintype "passive"))
      (node (ref "F1") (pin "2") (pinfunction "2_2") (pintype "bidirectional"))
      (node (ref "FUSE-0603") (pin "2") (pinfunction "2_2") (pintype "passive"))
      (node (ref "IC1") (pin "1") (pinfunction "VIN_1") (pintype "bidirectional"))
      (node (ref "IC1") (pin "3") (pinfunction "EN_3") (pintype "bidirectional"))
      (node (ref "IC2") (pin "1") (pinfunction "VIN_1") (pintype "bidirectional"))
      (node (ref "IC2") (pin "3") (pinfunction "EN_3") (pintype "bidirectional"))
      (node (ref "L2") (pin "1") (pinfunction "1_1") (pintype "passive"))
      (node (ref "Q1") (pin "1") (pinfunction "G_1") (pintype "passive"))
      (node (ref "Q5") (pin "3") (pinfunction "D_3") (pintype "passive"))
      (node (ref "U2") (pin "10") (pinfunction "VIN_10") (pintype "input"))
      (node (ref "U2") (pin "24") (pinfunction "VIN_P_24") (pintype "input"))
    )
    (net (code "81") (name "/VNEG-IN") (class "Default")
      (node (ref "C13") (pin "2") (pinfunction "2_2") (pintype "passive"))
      (node (ref "C16") (pin "2") (pinfunction "2_2") (pintype "passive"))
      (node (ref "D4") (pin "A") (pinfunction "A_A") (pintype "passive"))
      (node (ref "U2") (pin "16") (pinfunction "VCOM_PWR_16") (pintype "input"))
      (node (ref "U2") (pin "22") (pinfunction "PBKG_22") (pintype "bidirectional"))
      (node (ref "U2") (pin "26") (pinfunction "VN_26") (pintype "input"))
      (node (ref "U2") (pin "27") (pinfunction "VEE_IN_27") (pintype "input"))
    )
    (net (code "82") (name "/XCL") (class "Default")
      (node (ref "J1") (pin "8") (pinfunction "8_8") (pintype "passive"))
      (node (ref "U$1") (pin "109") (pinfunction "SDCLK_109") (pintype "bidirectional"))
    )
    (net (code "83") (name "/XLE") (class "Default")
      (node (ref "J1") (pin "10") (pinfunction "10_10") (pintype "passive"))
      (node (ref "U$1") (pin "107") (pinfunction "SDLE_107") (pintype "bidirectional"))
    )
    (net (code "84") (name "/XOE") (class "Default")
      (node (ref "J1") (pin "11") (pinfunction "11_11") (pintype "passive"))
      (node (ref "U$1") (pin "77") (pinfunction "SDOE_77") (pintype "bidirectional"))
    )
    (net (code "85") (name "/XSTL") (class "Default")
      (node (ref "J1") (pin "12") (pinfunction "12_12") (pintype "passive"))
      (node (ref "U$1") (pin "108") (pinfunction "SDSHR_108") (pintype "bidirectional"))
    )
    (net (code "86") (name "GND") (class "Default")
      (node (ref "C10") (pin "2") (pinfunction "2_2") (pintype "passive"))
      (node (ref "C11") (pin "2") (pinfunction "2_2") (pintype "passive"))
      (node (ref "C12") (pin "2") (pinfunction "2_2") (pintype "passive"))
      (node (ref "C13") (pin "1") (pinfunction "1_1") (pintype "passive"))
      (node (ref "C14") (pin "1") (pinfunction "1_1") (pintype "passive"))
      (node (ref "C15") (pin "1") (pinfunction "1_1") (pintype "passive"))
      (node (ref "C16") (pin "1") (pinfunction "1_1") (pintype "passive"))
      (node (ref "C18") (pin "1") (pinfunction "1_1") (pintype "passive"))
      (node (ref "C19") (pin "2") (pinfunction "2_2") (pintype "passive"))
      (node (ref "C2") (pin "2") (pinfunction "2_2") (pintype "passive"))
      (node (ref "C20") (pin "2") (pinfunction "2_2") (pintype "passive"))
      (node (ref "C22") (pin "1") (pinfunction "1_1") (pintype "passive"))
      (node (ref "C23") (pin "1") (pinfunction "1_1") (pintype "passive"))
      (node (ref "C24") (pin "2") (pinfunction "2_2") (pintype "passive"))
      (node (ref "C25") (pin "2") (pinfunction "2_2") (pintype "passive"))
      (node (ref "C26") (pin "2") (pinfunction "2_2") (pintype "passive"))
      (node (ref "C27") (pin "C") (pinfunction "-_C") (pintype "passive"))
      (node (ref "C28") (pin "2") (pinfunction "2_2") (pintype "passive"))
      (node (ref "C3") (pin "2") (pinfunction "2_2") (pintype "passive"))
      (node (ref "C31") (pin "2") (pinfunction "2_2") (pintype "passive"))
      (node (ref "C32") (pin "2") (pinfunction "2_2") (pintype "passive"))
      (node (ref "C34") (pin "2") (pinfunction "2_2") (pintype "passive"))
      (node (ref "C35") (pin "2") (pinfunction "2_2") (pintype "passive"))
      (node (ref "C36") (pin "C") (pinfunction "-_C") (pintype "passive"))
      (node (ref "C37") (pin "2") (pinfunction "2_2") (pintype "passive"))
      (node (ref "C4") (pin "2") (pinfunction "2_2") (pintype "passive"))
      (node (ref "C5") (pin "2") (pinfunction "2_2") (pintype "passive"))
      (node (ref "C6") (pin "1") (pinfunction "1_1") (pintype "passive"))
      (node (ref "C7") (pin "1") (pinfunction "1_1") (pintype "passive"))
      (node (ref "C8") (pin "2") (pinfunction "2_2") (pintype "passive"))
      (node (ref "C9") (pin "2") (pinfunction "2_2") (pintype "passive"))
      (node (ref "IC1") (pin "2") (pinfunction "GND_2") (pintype "bidirectional"))
      (node (ref "IC2") (pin "2") (pinfunction "GND_2") (pintype "bidirectional"))
      (node (ref "J1") (pin "26") (pinfunction "26_26") (pintype "passive"))
      (node (ref "J1") (pin "3") (pinfunction "3_3") (pintype "passive"))
      (node (ref "J1") (pin "32") (pinfunction "32_32") (pintype "passive"))
      (node (ref "J1") (pin "7") (pinfunction "7_7") (pintype "passive"))
      (node (ref "J1") (pin "9") (pinfunction "9_9") (pintype "passive"))
      (node (ref "J2") (pin "02") (pinfunction "02_02") (pintype "bidirectional"))
      (node (ref "J2") (pin "05") (pinfunction "05_05") (pintype "bidirectional"))
      (node (ref "J2") (pin "08") (pinfunction "08_08") (pintype "bidirectional"))
      (node (ref "J2") (pin "11") (pinfunction "11_11") (pintype "bidirectional"))
      (node (ref "J2") (pin "17") (pinfunction "17_17") (pintype "bidirectional"))
      (node (ref "J2") (pin "S1") (pinfunction "SHIELD_S1") (pintype "passive"))
      (node (ref "J2") (pin "S2") (pinfunction "SHIELD_S2") (pintype "passive"))
      (node (ref "J2") (pin "S3") (pinfunction "SHIELD_S3") (pintype "passive"))
      (node (ref "J2") (pin "S4") (pinfunction "SHIELD_S4") (pintype "passive"))
      (node (ref "J3") (pin "1") (pinfunction "GND_1") (pintype "power_in"))
      (node (ref "J3") (pin "12") (pinfunction "GND_12") (pintype "power_in"))
      (node (ref "J3") (pin "S1") (pinfunction "SHIELD_S1") (pintype "passive"))
      (node (ref "J3") (pin "S2") (pinfunction "SHIELD_S2") (pintype "passive"))
      (node (ref "J3") (pin "S3") (pinfunction "SHIELD_S3") (pintype "passive"))
      (node (ref "J3") (pin "S4") (pinfunction "SHIELD_S4") (pintype "passive"))
      (node (ref "J3") (pin "S5") (pinfunction "SHIELD_S5") (pintype "passive"))
      (node (ref "J3") (pin "S6") (pinfunction "SHIELD_S6") (pintype "passive"))
      (node (ref "J4") (pin "2") (pinfunction "2_2") (pintype "passive"))
      (node (ref "L1") (pin "2") (pinfunction "2_2") (pintype "passive"))
      (node (ref "Q3") (pin "2") (pinfunction "S_2") (pintype "passive"))
      (node (ref "Q4") (pin "2") (pinfunction "S_2") (pintype "passive"))
      (node (ref "R1") (pin "2") (pinfunction "2_2") (pintype "passive"))
      (node (ref "R11") (pin "2") (pinfunction "2_2") (pintype "passive"))
      (node (ref "R13") (pin "1") (pinfunction "1_1") (pintype "passive"))
      (node (ref "R2") (pin "2") (pinfunction "2_2") (pintype "passive"))
      (node (ref "R3") (pin "2") (pinfunction "2_2") (pintype "passive"))
      (node (ref "U$1") (pin "104") (pinfunction "GND6_104") (pintype "bidirectional"))
      (node (ref "U$1") (pin "113") (pinfunction "GND7_113") (pintype "bidirectional"))
      (node (ref "U$1") (pin "120") (pinfunction "GND8_120") (pintype "bidirectional"))
      (node (ref "U$1") (pin "125") (pinfunction "GND9_125") (pintype "bidirectional"))
      (node (ref "U$1") (pin "128") (pinfunction "GND10_128") (pintype "bidirectional"))
      (node (ref "U$1") (pin "21") (pinfunction "GND1_21") (pintype "bidirectional"))
      (node (ref "U$1") (pin "37") (pinfunction "GND-A_37") (pintype "bidirectional"))
      (node (ref "U$1") (pin "61") (pinfunction "GND2_61") (pintype "bidirectional"))
      (node (ref "U$1") (pin "76") (pinfunction "GND3_76") (pintype "bidirectional"))
      (node (ref "U$1") (pin "97") (pinfunction "GND4_97") (pintype "bidirectional"))
      (node (ref "U$3") (pin "P$100") (pinfunction "GND12_P$100") (pintype "bidirectional"))
      (node (ref "U$3") (pin "P$107") (pinfunction "GND13_P$107") (pintype "bidirectional"))
      (node (ref "U$3") (pin "P$118") (pinfunction "GND14_P$118") (pintype "bidirectional"))
      (node (ref "U$3") (pin "P$19") (pinfunction "GND4_P$19") (pintype "bidirectional"))
      (node (ref "U$3") (pin "P$26") (pinfunction "GND5_P$26") (pintype "bidirectional"))
      (node (ref "U$3") (pin "P$3") (pinfunction "GND_P$3") (pintype "bidirectional"))
      (node (ref "U$3") (pin "P$47") (pinfunction "GND6_P$47") (pintype "bidirectional"))
      (node (ref "U$3") (pin "P$6") (pinfunction "GND2_P$6") (pintype "bidirectional"))
      (node (ref "U$3") (pin "P$71") (pinfunction "GND7_P$71") (pintype "bidirectional"))
      (node (ref "U$3") (pin "P$81") (pinfunction "GND8_P$81") (pintype "bidirectional"))
      (node (ref "U$3") (pin "P$88") (pinfunction "GND9_P$88") (pintype "bidirectional"))
      (node (ref "U$3") (pin "P$89") (pinfunction "GND10_P$89") (pintype "bidirectional"))
      (node (ref "U$3") (pin "P$9") (pinfunction "GND3_P$9") (pintype "bidirectional"))
      (node (ref "U$3") (pin "P$90") (pinfunction "GND11_P$90") (pintype "bidirectional"))
      (node (ref "U$5") (pin "GND1") (pinfunction "P$1_GND1") (pintype "bidirectional"))
      (node (ref "U2") (pin "14") (pinfunction "VCOM_DIS_14") (pintype "input"))
      (node (ref "U2") (pin "32") (pinfunction "PGND2_32") (pintype "power_in"))
      (node (ref "U2") (pin "41") (pinfunction "PGDN1_41") (pintype "power_in"))
      (node (ref "U2") (pin "48") (pinfunction "AGND2_48") (pintype "power_in"))
      (node (ref "U2") (pin "6") (pinfunction "DGND_6") (pintype "power_in"))
      (node (ref "U2") (pin "8") (pinfunction "AGND1_8") (pintype "power_in"))
      (node (ref "U3") (pin "2") (pinfunction "GND_2") (pintype "power_in"))
    )
    (net (code "87") (name "Net-(C17-Pad2)") (class "Default")
      (node (ref "C17") (pin "2") (pinfunction "2_2") (pintype "passive"))
      (node (ref "D6") (pin "A") (pinfunction "A_A") (pintype "passive"))
      (node (ref "D7") (pin "C") (pinfunction "C_C") (pintype "passive"))
    )
    (net (code "88") (name "Net-(C27-+)") (class "Default")
      (node (ref "C27") (pin "A") (pinfunction "+_A") (pintype "passive"))
      (node (ref "C28") (pin "1") (pinfunction "1_1") (pintype "passive"))
      (node (ref "C5") (pin "1") (pinfunction "1_1") (pintype "passive"))
      (node (ref "F1") (pin "1") (pinfunction "1_1") (pintype "bidirectional"))
      (node (ref "U$3") (pin "P$85") (pinfunction "VCC-5V1_P$85") (pintype "bidirectional"))
      (node (ref "U$3") (pin "P$86") (pinfunction "VCC-5V2_P$86") (pintype "bidirectional"))
      (node (ref "U$3") (pin "P$87") (pinfunction "VCC-5V3_P$87") (pintype "bidirectional"))
    )
    (net (code "89") (name "Net-(C34-Pad1)") (class "Default")
      (node (ref "C34") (pin "1") (pinfunction "1_1") (pintype "passive"))
      (node (ref "FUSE-0603") (pin "1") (pinfunction "1_1") (pintype "passive"))
      (node (ref "J2") (pin "18") (pinfunction "18_18") (pintype "bidirectional"))
    )
    (net (code "90") (name "Net-(C36-+)") (class "Default")
      (node (ref "C35") (pin "1") (pinfunction "1_1") (pintype "passive"))
      (node (ref "C36") (pin "A") (pinfunction "+_A") (pintype "passive"))
      (node (ref "C37") (pin "1") (pinfunction "1_1") (pintype "passive"))
      (node (ref "F2") (pin "1") (pinfunction "1_1") (pintype "bidirectional"))
      (node (ref "Q5") (pin "2") (pinfunction "S_2") (pintype "passive"))
    )
    (net (code "91") (name "Net-(J3-CC1)") (class "Default")
      (node (ref "J3") (pin "3") (pinfunction "CC1_3") (pintype "passive"))
      (node (ref "R2") (pin "1") (pinfunction "1_1") (pintype "passive"))
    )
    (net (code "92") (name "Net-(J3-CC2)") (class "Default")
      (node (ref "J3") (pin "9") (pinfunction "CC2_9") (pintype "passive"))
      (node (ref "R1") (pin "1") (pinfunction "1_1") (pintype "passive"))
    )
    (net (code "93") (name "Net-(J5-Pad1)") (class "Default")
      (node (ref "J5") (pin "1") (pinfunction "1_1") (pintype "passive"))
      (node (ref "R4") (pin "2") (pinfunction "2_2") (pintype "passive"))
    )
    (net (code "94") (name "Net-(J5-Pad2)") (class "Default")
      (node (ref "J5") (pin "2") (pinfunction "2_2") (pintype "passive"))
      (node (ref "R7") (pin "2") (pinfunction "2_2") (pintype "passive"))
    )
    (net (code "95") (name "Net-(LT8912-XTAL0)") (class "Default")
      (node (ref "C29") (pin "2") (pinfunction "2_2") (pintype "passive"))
      (node (ref "LT8912") (pin "P53") (pinfunction "XTAL0_P53") (pintype "bidirectional"))
      (node (ref "Q2") (pin "1") (pinfunction "1_1") (pintype "passive"))
    )
    (net (code "96") (name "Net-(LT8912-XTALI)") (class "Default")
      (node (ref "C30") (pin "2") (pinfunction "2_2") (pintype "passive"))
      (node (ref "LT8912") (pin "P52") (pinfunction "XTALI_P52") (pintype "bidirectional"))
      (node (ref "Q2") (pin "2") (pinfunction "2_2") (pintype "passive"))
    )
    (net (code "97") (name "Net-(U$5-P$4)") (class "Default")
      (node (ref "F2") (pin "2") (pinfunction "2_2") (pintype "bidirectional"))
      (node (ref "U$5") (pin "VBUS1") (pinfunction "P$4_VBUS1") (pintype "bidirectional"))
    )
    (net (code "98") (name "Net-(U2-INT_LDO)") (class "Default")
      (node (ref "C14") (pin "2") (pinfunction "2_2") (pintype "passive"))
      (node (ref "U2") (pin "7") (pinfunction "INT_LDO_7") (pintype "output"))
    )
    (net (code "99") (name "Net-(U2-VDDH_DRV)") (class "Default")
      (node (ref "C21") (pin "1") (pinfunction "1_1") (pintype "passive"))
      (node (ref "U2") (pin "36") (pinfunction "VDDH_DRV_36") (pintype "output"))
    )
    (net (code "100") (name "Net-(U2-VEE_DRV)") (class "Default")
      (node (ref "C17") (pin "1") (pinfunction "1_1") (pintype "passive"))
      (node (ref "U2") (pin "28") (pinfunction "VEE_DRV_28") (pintype "output"))
    )
    (net (code "101") (name "Net-(U2-VNEG_IN)") (class "Default")
      (node (ref "C15") (pin "2") (pinfunction "2_2") (pintype "passive"))
      (node (ref "U2") (pin "4") (pinfunction "VNEG_IN_4") (pintype "input"))
    )
    (net (code "102") (name "Net-(U2-VN_SW)") (class "Default")
      (node (ref "D4") (pin "C") (pinfunction "C_C") (pintype "passive"))
      (node (ref "L1") (pin "1") (pinfunction "1_1") (pintype "passive"))
      (node (ref "U2") (pin "25") (pinfunction "VN_SW_25") (pintype "output"))
    )
    (net (code "103") (name "Net-(U2-VREF)") (class "Default")
      (node (ref "C7") (pin "2") (pinfunction "2_2") (pintype "passive"))
      (node (ref "U2") (pin "1") (pinfunction "VREF_1") (pintype "output"))
    )
    (net (code "104") (name "unconnected-(IC1-SNS-Pad4)") (class "Default")
      (node (ref "IC1") (pin "4") (pinfunction "SNS_4") (pintype "bidirectional"))
    )
    (net (code "105") (name "unconnected-(IC2-SNS-Pad4)") (class "Default")
      (node (ref "IC2") (pin "4") (pinfunction "SNS_4") (pintype "bidirectional"))
    )
    (net (code "106") (name "unconnected-(IC3-SNS-Pad4)") (class "Default")
      (node (ref "IC3") (pin "4") (pinfunction "SNS_4") (pintype "bidirectional"))
    )
    (net (code "107") (name "unconnected-(J1-Pad4)") (class "Default")
      (node (ref "J1") (pin "4") (pinfunction "4_4") (pintype "passive"))
    )
    (net (code "108") (name "unconnected-(J1-Pad5)") (class "Default")
      (node (ref "J1") (pin "5") (pinfunction "5_5") (pintype "passive"))
    )
    (net (code "109") (name "unconnected-(J1-Pad22)") (class "Default")
      (node (ref "J1") (pin "22") (pinfunction "22_22") (pintype "passive"))
    )
    (net (code "110") (name "unconnected-(J1-Pad23)") (class "Default")
      (node (ref "J1") (pin "23") (pinfunction "23_23") (pintype "passive"))
    )
    (net (code "111") (name "unconnected-(J1-Pad24)") (class "Default")
      (node (ref "J1") (pin "24") (pinfunction "24_24") (pintype "passive"))
    )
    (net (code "112") (name "unconnected-(J1-Pad25)") (class "Default")
      (node (ref "J1") (pin "25") (pinfunction "25_25") (pintype "passive"))
    )
    (net (code "113") (name "unconnected-(J1-Pad27)") (class "Default")
      (node (ref "J1") (pin "27") (pinfunction "27_27") (pintype "passive"))
    )
    (net (code "114") (name "unconnected-(J1-Pad30)") (class "Default")
      (node (ref "J1") (pin "30") (pinfunction "30_30") (pintype "passive"))
    )
    (net (code "115") (name "unconnected-(J1-Pad31)") (class "Default")
      (node (ref "J1") (pin "31") (pinfunction "31_31") (pintype "passive"))
    )
    (net (code "116") (name "unconnected-(J1-PadP1)") (class "Default")
      (node (ref "J1") (pin "P1") (pinfunction "P1_P1") (pintype "passive"))
    )
    (net (code "117") (name "unconnected-(J1-PadP2)") (class "Default")
      (node (ref "J1") (pin "P2") (pinfunction "P2_P2") (pintype "passive"))
    )
    (net (code "118") (name "unconnected-(J2-Pad13)") (class "Default")
      (node (ref "J2") (pin "13") (pinfunction "13_13") (pintype "bidirectional"))
    )
    (net (code "119") (name "unconnected-(J2-Pad14)") (class "Default")
      (node (ref "J2") (pin "14") (pinfunction "14_14") (pintype "bidirectional"))
    )
    (net (code "120") (name "unconnected-(J2-Pad15)") (class "Default")
      (node (ref "J2") (pin "15") (pinfunction "15_15") (pintype "bidirectional"))
    )
    (net (code "121") (name "unconnected-(J2-Pad16)") (class "Default")
      (node (ref "J2") (pin "16") (pinfunction "16_16") (pintype "bidirectional"))
    )
    (net (code "122") (name "unconnected-(J3-SBU1-Pad10)") (class "Default")
      (node (ref "J3") (pin "10") (pinfunction "SBU1_10") (pintype "passive"))
    )
    (net (code "123") (name "unconnected-(J3-SBU2-Pad4)") (class "Default")
      (node (ref "J3") (pin "4") (pinfunction "SBU2_4") (pintype "passive"))
    )
    (net (code "124") (name "unconnected-(LT8912-INT-PadP62)") (class "Default")
      (node (ref "LT8912") (pin "P62") (pinfunction "INT_P62") (pintype "bidirectional"))
    )
    (net (code "125") (name "unconnected-(LT8912-LPF-PadP19)") (class "Default")
      (node (ref "LT8912") (pin "P19") (pinfunction "LPF_P19") (pintype "bidirectional"))
    )
    (net (code "126") (name "unconnected-(LT8912-LVDSTX-CKN-PadP24)") (class "Default")
      (node (ref "LT8912") (pin "P24") (pinfunction "LVDSTX-CKN_P24") (pintype "bidirectional"))
    )
    (net (code "127") (name "unconnected-(LT8912-LVDSTX-CKP-PadP23)") (class "Default")
      (node (ref "LT8912") (pin "P23") (pinfunction "LVDSTX-CKP_P23") (pintype "bidirectional"))
    )
    (net (code "128") (name "unconnected-(LT8912-LVDSTX0-DN-PadP32)") (class "Default")
      (node (ref "LT8912") (pin "P32") (pinfunction "LVDSTX0-DN_P32") (pintype "bidirectional"))
    )
    (net (code "129") (name "unconnected-(LT8912-LVDSTX0-DP-PadP31)") (class "Default")
      (node (ref "LT8912") (pin "P31") (pinfunction "LVDSTX0-DP_P31") (pintype "bidirectional"))
    )
    (net (code "130") (name "unconnected-(LT8912-LVDSTX1-DN-PadP30)") (class "Default")
      (node (ref "LT8912") (pin "P30") (pinfunction "LVDSTX1-DN_P30") (pintype "bidirectional"))
    )
    (net (code "131") (name "unconnected-(LT8912-LVDSTX1-DP-PadP29)") (class "Default")
      (node (ref "LT8912") (pin "P29") (pinfunction "LVDSTX1-DP_P29") (pintype "bidirectional"))
    )
    (net (code "132") (name "unconnected-(LT8912-LVDSTX2-DN-PadP28)") (class "Default")
      (node (ref "LT8912") (pin "P28") (pinfunction "LVDSTX2-DN_P28") (pintype "bidirectional"))
    )
    (net (code "133") (name "unconnected-(LT8912-LVDSTX2-DP-PadP27)") (class "Default")
      (node (ref "LT8912") (pin "P27") (pinfunction "LVDSTX2-DP_P27") (pintype "bidirectional"))
    )
    (net (code "134") (name "unconnected-(LT8912-LVDSTX3-DN-PadP22)") (class "Default")
      (node (ref "LT8912") (pin "P22") (pinfunction "LVDSTX3-DN_P22") (pintype "bidirectional"))
    )
    (net (code "135") (name "unconnected-(LT8912-LVDSTX3-DP-PadP21)") (class "Default")
      (node (ref "LT8912") (pin "P21") (pinfunction "LVDSTX3-DP_P21") (pintype "bidirectional"))
    )
    (net (code "136") (name "unconnected-(LT8912-MIPI-RX2-DN-PadP9)") (class "Default")
      (node (ref "LT8912") (pin "P9") (pinfunction "MIPI-RX2-DN_P9") (pintype "bidirectional"))
    )
    (net (code "137") (name "unconnected-(LT8912-MIPI-RX2-DP-PadP8)") (class "Default")
      (node (ref "LT8912") (pin "P8") (pinfunction "MIPI-RX2-DP_P8") (pintype "bidirectional"))
    )
    (net (code "138") (name "unconnected-(LT8912-MIPI-RX3-DN-PadP11)") (class "Default")
      (node (ref "LT8912") (pin "P11") (pinfunction "MIPI-RX3-DN_P11") (pintype "bidirectional"))
    )
    (net (code "139") (name "unconnected-(LT8912-MIPI-RX3-DP-PadP10)") (class "Default")
      (node (ref "LT8912") (pin "P10") (pinfunction "MIPI-RX3-DP_P10") (pintype "bidirectional"))
    )
    (net (code "140") (name "unconnected-(LT8912-R6K-PadP12)") (class "Default")
      (node (ref "LT8912") (pin "P12") (pinfunction "R6K_P12") (pintype "bidirectional"))
    )
    (net (code "141") (name "unconnected-(LT8912-REF-CLK-PadP54)") (class "Default")
      (node (ref "LT8912") (pin "P54") (pinfunction "REF-CLK_P54") (pintype "bidirectional"))
    )
    (net (code "142") (name "unconnected-(LT8912-RESET-N-PadP63)") (class "Default")
      (node (ref "LT8912") (pin "P63") (pinfunction "RESET-N_P63") (pintype "bidirectional"))
    )
    (net (code "143") (name "unconnected-(LT8912-SCLK-I-PadP59)") (class "Default")
      (node (ref "LT8912") (pin "P59") (pinfunction "SCLK-I_P59") (pintype "bidirectional"))
    )
    (net (code "144") (name "unconnected-(LT8912-SD0-CEC-PadP57)") (class "Default")
      (node (ref "LT8912") (pin "P57") (pinfunction "SD0-CEC_P57") (pintype "bidirectional"))
    )
    (net (code "145") (name "unconnected-(LT8912-USB-DN-PadP36)") (class "Default")
      (node (ref "LT8912") (pin "P36") (pinfunction "USB-DN_P36") (pintype "bidirectional"))
    )
    (net (code "146") (name "unconnected-(LT8912-USB-DP-PadP35)") (class "Default")
      (node (ref "LT8912") (pin "P35") (pinfunction "USB-DP_P35") (pintype "bidirectional"))
    )
    (net (code "147") (name "unconnected-(LT8912-USB-ID-PadP15)") (class "Default")
      (node (ref "LT8912") (pin "P15") (pinfunction "USB-ID_P15") (pintype "bidirectional"))
    )
    (net (code "148") (name "unconnected-(LT8912-VBUS-PadP14)") (class "Default")
      (node (ref "LT8912") (pin "P14") (pinfunction "VBUS_P14") (pintype "bidirectional"))
    )
    (net (code "149") (name "unconnected-(LT8912-VCCA-HDMIPLL-PadP18)") (class "Default")
      (node (ref "LT8912") (pin "P18") (pinfunction "VCCA-HDMIPLL_P18") (pintype "bidirectional"))
    )
    (net (code "150") (name "unconnected-(LT8912-VCCA-LVDSPLL-PadP51)") (class "Default")
      (node (ref "LT8912") (pin "P51") (pinfunction "VCCA-LVDSPLL_P51") (pintype "bidirectional"))
    )
    (net (code "151") (name "unconnected-(LT8912-VCCA-LVDSTX-PadP25)") (class "Default")
      (node (ref "LT8912") (pin "P25") (pinfunction "VCCA-LVDSTX_P25") (pintype "bidirectional"))
    )
    (net (code "152") (name "unconnected-(LT8912-VCCA-SYSCLK-PadP49)") (class "Default")
      (node (ref "LT8912") (pin "P49") (pinfunction "VCCA-SYSCLK_P49") (pintype "bidirectional"))
    )
    (net (code "153") (name "unconnected-(LT8912-VSSA-SYSCLK-PadP48)") (class "Default")
      (node (ref "LT8912") (pin "P48") (pinfunction "VSSA-SYSCLK_P48") (pintype "bidirectional"))
    )
    (net (code "154") (name "unconnected-(LT8912-WS-I-PadP58)") (class "Default")
      (node (ref "LT8912") (pin "P58") (pinfunction "WS-I_P58") (pintype "bidirectional"))
    )
    (net (code "155") (name "unconnected-(U$1-BORDER-SHD-N-Pad70)") (class "Default")
      (node (ref "U$1") (pin "70") (pinfunction "BORDER-SHD-N_70") (pintype "bidirectional"))
    )
    (net (code "156") (name "unconnected-(U$1-GD-OE-Pad72)") (class "Default")
      (node (ref "U$1") (pin "72") (pinfunction "GD-OE_72") (pintype "bidirectional"))
    )
    (net (code "157") (name "unconnected-(U$1-GD-RL-Pad73)") (class "Default")
      (node (ref "U$1") (pin "73") (pinfunction "GD-RL_73") (pintype "bidirectional"))
    )
    (net (code "158") (name "unconnected-(U$1-GND5-Pad100)") (class "Default")
      (node (ref "U$1") (pin "100") (pinfunction "GND5_100") (pintype "bidirectional"))
    )
    (net (code "159") (name "unconnected-(U$1-HDB0-Pad15)") (class "Default")
      (node (ref "U$1") (pin "15") (pinfunction "HDB0_15") (pintype "bidirectional"))
    )
    (net (code "160") (name "unconnected-(U$1-HDB1-Pad16)") (class "Default")
      (node (ref "U$1") (pin "16") (pinfunction "HDB1_16") (pintype "bidirectional"))
    )
    (net (code "161") (name "unconnected-(U$1-HDB2-Pad17)") (class "Default")
      (node (ref "U$1") (pin "17") (pinfunction "HDB2_17") (pintype "bidirectional"))
    )
    (net (code "162") (name "unconnected-(U$1-HDB3-Pad18)") (class "Default")
      (node (ref "U$1") (pin "18") (pinfunction "HDB3_18") (pintype "bidirectional"))
    )
    (net (code "163") (name "unconnected-(U$1-HDB4-Pad19)") (class "Default")
      (node (ref "U$1") (pin "19") (pinfunction "HDB4_19") (pintype "bidirectional"))
    )
    (net (code "164") (name "unconnected-(U$1-HDB5-Pad22)") (class "Default")
      (node (ref "U$1") (pin "22") (pinfunction "HDB5_22") (pintype "bidirectional"))
    )
    (net (code "165") (name "unconnected-(U$1-HDB6-Pad23)") (class "Default")
      (node (ref "U$1") (pin "23") (pinfunction "HDB6_23") (pintype "bidirectional"))
    )
    (net (code "166") (name "unconnected-(U$1-HDB7-Pad24)") (class "Default")
      (node (ref "U$1") (pin "24") (pinfunction "HDB7_24") (pintype "bidirectional"))
    )
    (net (code "167") (name "unconnected-(U$1-HDB8-Pad25)") (class "Default")
      (node (ref "U$1") (pin "25") (pinfunction "HDB8_25") (pintype "bidirectional"))
    )
    (net (code "168") (name "unconnected-(U$1-HDB9-Pad26)") (class "Default")
      (node (ref "U$1") (pin "26") (pinfunction "HDB9_26") (pintype "bidirectional"))
    )
    (net (code "169") (name "unconnected-(U$1-HDB10-Pad27)") (class "Default")
      (node (ref "U$1") (pin "27") (pinfunction "HDB10_27") (pintype "bidirectional"))
    )
    (net (code "170") (name "unconnected-(U$1-HDB11-Pad28)") (class "Default")
      (node (ref "U$1") (pin "28") (pinfunction "HDB11_28") (pintype "bidirectional"))
    )
    (net (code "171") (name "unconnected-(U$1-HDB12-Pad29)") (class "Default")
      (node (ref "U$1") (pin "29") (pinfunction "HDB12_29") (pintype "bidirectional"))
    )
    (net (code "172") (name "unconnected-(U$1-HDB13-Pad30)") (class "Default")
      (node (ref "U$1") (pin "30") (pinfunction "HDB13_30") (pintype "bidirectional"))
    )
    (net (code "173") (name "unconnected-(U$1-HDB14-Pad31)") (class "Default")
      (node (ref "U$1") (pin "31") (pinfunction "HDB14_31") (pintype "bidirectional"))
    )
    (net (code "174") (name "unconnected-(U$1-HDB15-Pad32)") (class "Default")
      (node (ref "U$1") (pin "32") (pinfunction "HDB15_32") (pintype "bidirectional"))
    )
    (net (code "175") (name "unconnected-(U$1-HOST-DC-Pad12)") (class "Default")
      (node (ref "U$1") (pin "12") (pinfunction "HOST-DC_12") (pintype "bidirectional"))
    )
    (net (code "176") (name "unconnected-(U$1-HOST-HIRQ-Pad14)") (class "Default")
      (node (ref "U$1") (pin "14") (pinfunction "HOST-HIRQ_14") (pintype "bidirectional"))
    )
    (net (code "177") (name "unconnected-(U$1-HOST-HRDY-Pad13)") (class "Default")
      (node (ref "U$1") (pin "13") (pinfunction "HOST-HRDY_13") (pintype "bidirectional"))
    )
    (net (code "178") (name "unconnected-(U$1-I2C-SCL-Pad110)") (class "Default")
      (node (ref "U$1") (pin "110") (pinfunction "I2C-SCL_110") (pintype "bidirectional"))
    )
    (net (code "179") (name "unconnected-(U$1-I2C-SDA-Pad111)") (class "Default")
      (node (ref "U$1") (pin "111") (pinfunction "I2C-SDA_111") (pintype "bidirectional"))
    )
    (net (code "180") (name "unconnected-(U$1-P$9-Pad9)") (class "Default")
      (node (ref "U$1") (pin "9") (pinfunction "P$9_9") (pintype "bidirectional"))
    )
    (net (code "181") (name "unconnected-(U$1-P$10-Pad10)") (class "Default")
      (node (ref "U$1") (pin "10") (pinfunction "P$10_10") (pintype "bidirectional"))
    )
    (net (code "182") (name "unconnected-(U$1-P$11-Pad11)") (class "Default")
      (node (ref "U$1") (pin "11") (pinfunction "P$11_11") (pintype "bidirectional"))
    )
    (net (code "183") (name "unconnected-(U$1-P$34-Pad34)") (class "Default")
      (node (ref "U$1") (pin "34") (pinfunction "P$34_34") (pintype "bidirectional"))
    )
    (net (code "184") (name "unconnected-(U$1-P$35-Pad35)") (class "Default")
      (node (ref "U$1") (pin "35") (pinfunction "P$35_35") (pintype "bidirectional"))
    )
    (net (code "185") (name "unconnected-(U$1-P$36-Pad36)") (class "Default")
      (node (ref "U$1") (pin "36") (pinfunction "P$36_36") (pintype "bidirectional"))
    )
    (net (code "186") (name "unconnected-(U$1-P$38-Pad38)") (class "Default")
      (node (ref "U$1") (pin "38") (pinfunction "P$38_38") (pintype "bidirectional"))
    )
    (net (code "187") (name "unconnected-(U$1-P$39-Pad39)") (class "Default")
      (node (ref "U$1") (pin "39") (pinfunction "P$39_39") (pintype "bidirectional"))
    )
    (net (code "188") (name "unconnected-(U$1-P$40-Pad40)") (class "Default")
      (node (ref "U$1") (pin "40") (pinfunction "P$40_40") (pintype "bidirectional"))
    )
    (net (code "189") (name "unconnected-(U$1-P$41-Pad41)") (class "Default")
      (node (ref "U$1") (pin "41") (pinfunction "P$41_41") (pintype "bidirectional"))
    )
    (net (code "190") (name "unconnected-(U$1-P$42-Pad42)") (class "Default")
      (node (ref "U$1") (pin "42") (pinfunction "P$42_42") (pintype "bidirectional"))
    )
    (net (code "191") (name "unconnected-(U$1-P$43-Pad43)") (class "Default")
      (node (ref "U$1") (pin "43") (pinfunction "P$43_43") (pintype "bidirectional"))
    )
    (net (code "192") (name "unconnected-(U$1-P$44-Pad44)") (class "Default")
      (node (ref "U$1") (pin "44") (pinfunction "P$44_44") (pintype "bidirectional"))
    )
    (net (code "193") (name "unconnected-(U$1-P$46-Pad46)") (class "Default")
      (node (ref "U$1") (pin "46") (pinfunction "P$46_46") (pintype "bidirectional"))
    )
    (net (code "194") (name "unconnected-(U$1-P$47-Pad47)") (class "Default")
      (node (ref "U$1") (pin "47") (pinfunction "P$47_47") (pintype "bidirectional"))
    )
    (net (code "195") (name "unconnected-(U$1-P$49-Pad49)") (class "Default")
      (node (ref "U$1") (pin "49") (pinfunction "P$49_49") (pintype "bidirectional"))
    )
    (net (code "196") (name "unconnected-(U$1-P$50-Pad50)") (class "Default")
      (node (ref "U$1") (pin "50") (pinfunction "P$50_50") (pintype "bidirectional"))
    )
    (net (code "197") (name "unconnected-(U$1-P$51-Pad51)") (class "Default")
      (node (ref "U$1") (pin "51") (pinfunction "P$51_51") (pintype "bidirectional"))
    )
    (net (code "198") (name "unconnected-(U$1-P$52-Pad52)") (class "Default")
      (node (ref "U$1") (pin "52") (pinfunction "P$52_52") (pintype "bidirectional"))
    )
    (net (code "199") (name "unconnected-(U$1-P$53-Pad53)") (class "Default")
      (node (ref "U$1") (pin "53") (pinfunction "P$53_53") (pintype "bidirectional"))
    )
    (net (code "200") (name "unconnected-(U$1-P$54-Pad54)") (class "Default")
      (node (ref "U$1") (pin "54") (pinfunction "P$54_54") (pintype "bidirectional"))
    )
    (net (code "201") (name "unconnected-(U$1-P$55-Pad55)") (class "Default")
      (node (ref "U$1") (pin "55") (pinfunction "P$55_55") (pintype "bidirectional"))
    )
    (net (code "202") (name "unconnected-(U$1-P$56-Pad56)") (class "Default")
      (node (ref "U$1") (pin "56") (pinfunction "P$56_56") (pintype "bidirectional"))
    )
    (net (code "203") (name "unconnected-(U$1-P$57-Pad57)") (class "Default")
      (node (ref "U$1") (pin "57") (pinfunction "P$57_57") (pintype "bidirectional"))
    )
    (net (code "204") (name "unconnected-(U$1-P$58-Pad58)") (class "Default")
      (node (ref "U$1") (pin "58") (pinfunction "P$58_58") (pintype "bidirectional"))
    )
    (net (code "205") (name "unconnected-(U$1-P$59-Pad59)") (class "Default")
      (node (ref "U$1") (pin "59") (pinfunction "P$59_59") (pintype "bidirectional"))
    )
    (net (code "206") (name "unconnected-(U$1-P$95-Pad95)") (class "Default")
      (node (ref "U$1") (pin "95") (pinfunction "P$95_95") (pintype "bidirectional"))
    )
    (net (code "207") (name "unconnected-(U$1-P$96-Pad96)") (class "Default")
      (node (ref "U$1") (pin "96") (pinfunction "P$96_96") (pintype "bidirectional"))
    )
    (net (code "208") (name "unconnected-(U$1-P$112-Pad112)") (class "Default")
      (node (ref "U$1") (pin "112") (pinfunction "P$112_112") (pintype "bidirectional"))
    )
    (net (code "209") (name "unconnected-(U$1-P$114-Pad114)") (class "Default")
      (node (ref "U$1") (pin "114") (pinfunction "P$114_114") (pintype "bidirectional"))
    )
    (net (code "210") (name "unconnected-(U$1-P$121-Pad121)") (class "Default")
      (node (ref "U$1") (pin "121") (pinfunction "P$121_121") (pintype "bidirectional"))
    )
    (net (code "211") (name "unconnected-(U$1-P$127-Pad127)") (class "Default")
      (node (ref "U$1") (pin "127") (pinfunction "P$127_127") (pintype "bidirectional"))
    )
    (net (code "212") (name "unconnected-(U$1-PWR0-Pad62)") (class "Default")
      (node (ref "U$1") (pin "62") (pinfunction "PWR0_62") (pintype "bidirectional"))
    )
    (net (code "213") (name "unconnected-(U$1-PWR1-Pad63)") (class "Default")
      (node (ref "U$1") (pin "63") (pinfunction "PWR1_63") (pintype "bidirectional"))
    )
    (net (code "214") (name "unconnected-(U$1-PWR2-Pad64)") (class "Default")
      (node (ref "U$1") (pin "64") (pinfunction "PWR2_64") (pintype "bidirectional"))
    )
    (net (code "215") (name "unconnected-(U$1-PWR3-Pad65)") (class "Default")
      (node (ref "U$1") (pin "65") (pinfunction "PWR3_65") (pintype "bidirectional"))
    )
    (net (code "216") (name "unconnected-(U$1-PWR4-Pad66)") (class "Default")
      (node (ref "U$1") (pin "66") (pinfunction "PWR4_66") (pintype "bidirectional"))
    )
    (net (code "217") (name "unconnected-(U$1-PWR5-Pad67)") (class "Default")
      (node (ref "U$1") (pin "67") (pinfunction "PWR5_67") (pintype "bidirectional"))
    )
    (net (code "218") (name "unconnected-(U$1-PWR6-Pad68)") (class "Default")
      (node (ref "U$1") (pin "68") (pinfunction "PWR6_68") (pintype "bidirectional"))
    )
    (net (code "219") (name "unconnected-(U$1-PWR7-Pad69)") (class "Default")
      (node (ref "U$1") (pin "69") (pinfunction "PWR7_69") (pintype "bidirectional"))
    )
    (net (code "220") (name "unconnected-(U$1-RESET-N-Pad2)") (class "Default")
      (node (ref "U$1") (pin "2") (pinfunction "RESET-N_2") (pintype "bidirectional"))
    )
    (net (code "221") (name "unconnected-(U$1-SDCE-N0-Pad78)") (class "Default")
      (node (ref "U$1") (pin "78") (pinfunction "SDCE-N0_78") (pintype "bidirectional"))
    )
    (net (code "222") (name "unconnected-(U$1-SDCE-N1-Pad79)") (class "Default")
      (node (ref "U$1") (pin "79") (pinfunction "SDCE-N1_79") (pintype "bidirectional"))
    )
    (net (code "223") (name "unconnected-(U$1-SDCE-N2-Pad80)") (class "Default")
      (node (ref "U$1") (pin "80") (pinfunction "SDCE-N2_80") (pintype "bidirectional"))
    )
    (net (code "224") (name "unconnected-(U$1-SDCE-N3-Pad81)") (class "Default")
      (node (ref "U$1") (pin "81") (pinfunction "SDCE-N3_81") (pintype "bidirectional"))
    )
    (net (code "225") (name "unconnected-(U$1-SDDO8-Pad90)") (class "Default")
      (node (ref "U$1") (pin "90") (pinfunction "SDDO8_90") (pintype "bidirectional"))
    )
    (net (code "226") (name "unconnected-(U$1-SDDO9-Pad91)") (class "Default")
      (node (ref "U$1") (pin "91") (pinfunction "SDDO9_91") (pintype "bidirectional"))
    )
    (net (code "227") (name "unconnected-(U$1-SDDO10-Pad92)") (class "Default")
      (node (ref "U$1") (pin "92") (pinfunction "SDDO10_92") (pintype "bidirectional"))
    )
    (net (code "228") (name "unconnected-(U$1-SDDO11-Pad93)") (class "Default")
      (node (ref "U$1") (pin "93") (pinfunction "SDDO11_93") (pintype "bidirectional"))
    )
    (net (code "229") (name "unconnected-(U$1-SDDO12-Pad101)") (class "Default")
      (node (ref "U$1") (pin "101") (pinfunction "SDDO12_101") (pintype "bidirectional"))
    )
    (net (code "230") (name "unconnected-(U$1-SDDO13-Pad102)") (class "Default")
      (node (ref "U$1") (pin "102") (pinfunction "SDDO13_102") (pintype "bidirectional"))
    )
    (net (code "231") (name "unconnected-(U$1-SDDO14-Pad103)") (class "Default")
      (node (ref "U$1") (pin "103") (pinfunction "SDDO14_103") (pintype "bidirectional"))
    )
    (net (code "232") (name "unconnected-(U$1-SDDO15-Pad106)") (class "Default")
      (node (ref "U$1") (pin "106") (pinfunction "SDDO15_106") (pintype "bidirectional"))
    )
    (net (code "233") (name "unconnected-(U$1-SPI2-CS-Pad119)") (class "Default")
      (node (ref "U$1") (pin "119") (pinfunction "SPI2-CS_119") (pintype "bidirectional"))
    )
    (net (code "234") (name "unconnected-(U$1-SPI2-SCK-Pad122)") (class "Default")
      (node (ref "U$1") (pin "122") (pinfunction "SPI2-SCK_122") (pintype "bidirectional"))
    )
    (net (code "235") (name "unconnected-(U$1-SPI2-SI-Pad123)") (class "Default")
      (node (ref "U$1") (pin "123") (pinfunction "SPI2-SI_123") (pintype "bidirectional"))
    )
    (net (code "236") (name "unconnected-(U$1-SPI2-SO-Pad124)") (class "Default")
      (node (ref "U$1") (pin "124") (pinfunction "SPI2-SO_124") (pintype "bidirectional"))
    )
    (net (code "237") (name "unconnected-(U$1-TEST-CFG0-Pad4)") (class "Default")
      (node (ref "U$1") (pin "4") (pinfunction "TEST-CFG0_4") (pintype "bidirectional"))
    )
    (net (code "238") (name "unconnected-(U$1-TEST-CFG1-Pad5)") (class "Default")
      (node (ref "U$1") (pin "5") (pinfunction "TEST-CFG1_5") (pintype "bidirectional"))
    )
    (net (code "239") (name "unconnected-(U$1-TEST-CFG2-Pad6)") (class "Default")
      (node (ref "U$1") (pin "6") (pinfunction "TEST-CFG2_6") (pintype "bidirectional"))
    )
    (net (code "240") (name "unconnected-(U$1-TEST-EN-Pad3)") (class "Default")
      (node (ref "U$1") (pin "3") (pinfunction "TEST-EN_3") (pintype "bidirectional"))
    )
    (net (code "241") (name "unconnected-(U$1-UART-RX-Pad8)") (class "Default")
      (node (ref "U$1") (pin "8") (pinfunction "UART-RX_8") (pintype "bidirectional"))
    )
    (net (code "242") (name "unconnected-(U$1-UART-TX-Pad7)") (class "Default")
      (node (ref "U$1") (pin "7") (pinfunction "UART-TX_7") (pintype "bidirectional"))
    )
    (net (code "243") (name "unconnected-(U$1-VCC-SDR-Pad105)") (class "Default")
      (node (ref "U$1") (pin "105") (pinfunction "VCC-SDR_105") (pintype "bidirectional"))
    )
    (net (code "244") (name "unconnected-(U$1-VCC-SDR2-Pad98)") (class "Default")
      (node (ref "U$1") (pin "98") (pinfunction "VCC-SDR2_98") (pintype "bidirectional"))
    )
    (net (code "245") (name "unconnected-(U$1-VCC33A-HRST-Pad48)") (class "Default")
      (node (ref "U$1") (pin "48") (pinfunction "VCC33A-HRST_48") (pintype "bidirectional"))
    )
    (net (code "246") (name "unconnected-(U$3-3V3-PadP$84)") (class "Default")
      (node (ref "U$3") (pin "P$84") (pinfunction "3V3_P$84") (pintype "bidirectional"))
    )
    (net (code "247") (name "unconnected-(U$3-FSPI-D2-PadP$24)") (class "Default")
      (node (ref "U$3") (pin "P$24") (pinfunction "FSPI-D2_P$24") (pintype "bidirectional"))
    )
    (net (code "248") (name "unconnected-(U$3-FSPI-D3-PadP$25)") (class "Default")
      (node (ref "U$3") (pin "P$25") (pinfunction "FSPI-D3_P$25") (pintype "bidirectional"))
    )
    (net (code "249") (name "unconnected-(U$3-PadP$10)") (class "Default")
      (node (ref "U$3") (pin "P$10") (pinfunction "P$10_P$10") (pintype "bidirectional"))
    )
    (net (code "250") (name "unconnected-(U$3-PadP$11)") (class "Default")
      (node (ref "U$3") (pin "P$11") (pinfunction "P$11_P$11") (pintype "bidirectional"))
    )
    (net (code "251") (name "unconnected-(U$3-PadP$12)") (class "Default")
      (node (ref "U$3") (pin "P$12") (pinfunction "P$12_P$12") (pintype "bidirectional"))
    )
    (net (code "252") (name "unconnected-(U$3-PadP$13)") (class "Default")
      (node (ref "U$3") (pin "P$13") (pinfunction "P$13_P$13") (pintype "bidirectional"))
    )
    (net (code "253") (name "unconnected-(U$3-PadP$14)") (class "Default")
      (node (ref "U$3") (pin "P$14") (pinfunction "P$14_P$14") (pintype "bidirectional"))
    )
    (net (code "254") (name "unconnected-(U$3-PadP$27)") (class "Default")
      (node (ref "U$3") (pin "P$27") (pinfunction "P$27_P$27") (pintype "bidirectional"))
    )
    (net (code "255") (name "unconnected-(U$3-PadP$29)") (class "Default")
      (node (ref "U$3") (pin "P$29") (pinfunction "P$29_P$29") (pintype "bidirectional"))
    )
    (net (code "256") (name "unconnected-(U$3-PadP$31)") (class "Default")
      (node (ref "U$3") (pin "P$31") (pinfunction "P$31_P$31") (pintype "bidirectional"))
    )
    (net (code "257") (name "unconnected-(U$3-PadP$32)") (class "Default")
      (node (ref "U$3") (pin "P$32") (pinfunction "P$32_P$32") (pintype "bidirectional"))
    )
    (net (code "258") (name "unconnected-(U$3-PadP$33)") (class "Default")
      (node (ref "U$3") (pin "P$33") (pinfunction "P$33_P$33") (pintype "bidirectional"))
    )
    (net (code "259") (name "unconnected-(U$3-PadP$34)") (class "Default")
      (node (ref "U$3") (pin "P$34") (pinfunction "P$34_P$34") (pintype "bidirectional"))
    )
    (net (code "260") (name "unconnected-(U$3-PadP$35)") (class "Default")
      (node (ref "U$3") (pin "P$35") (pinfunction "P$35_P$35") (pintype "bidirectional"))
    )
    (net (code "261") (name "unconnected-(U$3-PadP$36)") (class "Default")
      (node (ref "U$3") (pin "P$36") (pinfunction "P$36_P$36") (pintype "bidirectional"))
    )
    (net (code "262") (name "unconnected-(U$3-PadP$37)") (class "Default")
      (node (ref "U$3") (pin "P$37") (pinfunction "P$37_P$37") (pintype "bidirectional"))
    )
    (net (code "263") (name "unconnected-(U$3-PadP$38)") (class "Default")
      (node (ref "U$3") (pin "P$38") (pinfunction "P$38_P$38") (pintype "bidirectional"))
    )
    (net (code "264") (name "unconnected-(U$3-PadP$39)") (class "Default")
      (node (ref "U$3") (pin "P$39") (pinfunction "P$39_P$39") (pintype "bidirectional"))
    )
    (net (code "265") (name "unconnected-(U$3-PadP$40)") (class "Default")
      (node (ref "U$3") (pin "P$40") (pinfunction "P$40_P$40") (pintype "bidirectional"))
    )
    (net (code "266") (name "unconnected-(U$3-PadP$41)") (class "Default")
      (node (ref "U$3") (pin "P$41") (pinfunction "P$41_P$41") (pintype "bidirectional"))
    )
    (net (code "267") (name "unconnected-(U$3-PadP$42)") (class "Default")
      (node (ref "U$3") (pin "P$42") (pinfunction "P$42_P$42") (pintype "bidirectional"))
    )
    (net (code "268") (name "unconnected-(U$3-PadP$43)") (class "Default")
      (node (ref "U$3") (pin "P$43") (pinfunction "P$43_P$43") (pintype "bidirectional"))
    )
    (net (code "269") (name "unconnected-(U$3-PadP$44)") (class "Default")
      (node (ref "U$3") (pin "P$44") (pinfunction "P$44_P$44") (pintype "bidirectional"))
    )
    (net (code "270") (name "unconnected-(U$3-PadP$45)") (class "Default")
      (node (ref "U$3") (pin "P$45") (pinfunction "P$45_P$45") (pintype "bidirectional"))
    )
    (net (code "271") (name "unconnected-(U$3-PadP$46)") (class "Default")
      (node (ref "U$3") (pin "P$46") (pinfunction "P$46_P$46") (pintype "bidirectional"))
    )
    (net (code "272") (name "unconnected-(U$3-PadP$48)") (class "Default")
      (node (ref "U$3") (pin "P$48") (pinfunction "P$48_P$48") (pintype "bidirectional"))
    )
    (net (code "273") (name "unconnected-(U$3-PadP$49)") (class "Default")
      (node (ref "U$3") (pin "P$49") (pinfunction "P$49_P$49") (pintype "bidirectional"))
    )
    (net (code "274") (name "unconnected-(U$3-PadP$50)") (class "Default")
      (node (ref "U$3") (pin "P$50") (pinfunction "P$50_P$50") (pintype "bidirectional"))
    )
    (net (code "275") (name "unconnected-(U$3-PadP$51)") (class "Default")
      (node (ref "U$3") (pin "P$51") (pinfunction "P$51_P$51") (pintype "bidirectional"))
    )
    (net (code "276") (name "unconnected-(U$3-PadP$52)") (class "Default")
      (node (ref "U$3") (pin "P$52") (pinfunction "P$52_P$52") (pintype "bidirectional"))
    )
    (net (code "277") (name "unconnected-(U$3-PadP$53)") (class "Default")
      (node (ref "U$3") (pin "P$53") (pinfunction "P$53_P$53") (pintype "bidirectional"))
    )
    (net (code "278") (name "unconnected-(U$3-PadP$54)") (class "Default")
      (node (ref "U$3") (pin "P$54") (pinfunction "P$54_P$54") (pintype "bidirectional"))
    )
    (net (code "279") (name "unconnected-(U$3-PadP$55)") (class "Default")
      (node (ref "U$3") (pin "P$55") (pinfunction "P$55_P$55") (pintype "bidirectional"))
    )
    (net (code "280") (name "unconnected-(U$3-PadP$65)") (class "Default")
      (node (ref "U$3") (pin "P$65") (pinfunction "P$65_P$65") (pintype "bidirectional"))
    )
    (net (code "281") (name "unconnected-(U$3-PadP$66)") (class "Default")
      (node (ref "U$3") (pin "P$66") (pinfunction "P$66_P$66") (pintype "bidirectional"))
    )
    (net (code "282") (name "unconnected-(U$3-PadP$67)") (class "Default")
      (node (ref "U$3") (pin "P$67") (pinfunction "P$67_P$67") (pintype "bidirectional"))
    )
    (net (code "283") (name "unconnected-(U$3-PadP$72)") (class "Default")
      (node (ref "U$3") (pin "P$72") (pinfunction "P$72_P$72") (pintype "bidirectional"))
    )
    (net (code "284") (name "unconnected-(U$3-PadP$73)") (class "Default")
      (node (ref "U$3") (pin "P$73") (pinfunction "P$73_P$73") (pintype "bidirectional"))
    )
    (net (code "285") (name "unconnected-(U$3-PadP$74)") (class "Default")
      (node (ref "U$3") (pin "P$74") (pinfunction "P$74_P$74") (pintype "bidirectional"))
    )
    (net (code "286") (name "unconnected-(U$3-PadP$75)") (class "Default")
      (node (ref "U$3") (pin "P$75") (pinfunction "P$75_P$75") (pintype "bidirectional"))
    )
    (net (code "287") (name "unconnected-(U$3-PadP$76)") (class "Default")
      (node (ref "U$3") (pin "P$76") (pinfunction "P$76_P$76") (pintype "bidirectional"))
    )
    (net (code "288") (name "unconnected-(U$3-PadP$77)") (class "Default")
      (node (ref "U$3") (pin "P$77") (pinfunction "P$77_P$77") (pintype "bidirectional"))
    )
    (net (code "289") (name "unconnected-(U$3-PadP$78)") (class "Default")
      (node (ref "U$3") (pin "P$78") (pinfunction "P$78_P$78") (pintype "bidirectional"))
    )
    (net (code "290") (name "unconnected-(U$3-PadP$79)") (class "Default")
      (node (ref "U$3") (pin "P$79") (pinfunction "P$79_P$79") (pintype "bidirectional"))
    )
    (net (code "291") (name "unconnected-(U$3-PadP$80)") (class "Default")
      (node (ref "U$3") (pin "P$80") (pinfunction "P$80_P$80") (pintype "bidirectional"))
    )
    (net (code "292") (name "unconnected-(U$3-PadP$82)") (class "Default")
      (node (ref "U$3") (pin "P$82") (pinfunction "P$82_P$82") (pintype "bidirectional"))
    )
    (net (code "293") (name "unconnected-(U$3-PadP$83)") (class "Default")
      (node (ref "U$3") (pin "P$83") (pinfunction "P$83_P$83") (pintype "bidirectional"))
    )
    (net (code "294") (name "unconnected-(U$3-PadP$91)") (class "Default")
      (node (ref "U$3") (pin "P$91") (pinfunction "P$91_P$91") (pintype "bidirectional"))
    )
    (net (code "295") (name "unconnected-(U$3-PadP$96)") (class "Default")
      (node (ref "U$3") (pin "P$96") (pinfunction "P$96_P$96") (pintype "bidirectional"))
    )
    (net (code "296") (name "unconnected-(U$3-PadP$98)") (class "Default")
      (node (ref "U$3") (pin "P$98") (pinfunction "P$98_P$98") (pintype "bidirectional"))
    )
    (net (code "297") (name "unconnected-(U$3-PadP$99)") (class "Default")
      (node (ref "U$3") (pin "P$99") (pinfunction "P$99_P$99") (pintype "bidirectional"))
    )
    (net (code "298") (name "unconnected-(U$3-PadP$114)") (class "Default")
      (node (ref "U$3") (pin "P$114") (pinfunction "P$114_P$114") (pintype "bidirectional"))
    )
    (net (code "299") (name "unconnected-(U$3-PadP$115)") (class "Default")
      (node (ref "U$3") (pin "P$115") (pinfunction "P$115_P$115") (pintype "bidirectional"))
    )
    (net (code "300") (name "unconnected-(U$3-PadP$116)") (class "Default")
      (node (ref "U$3") (pin "P$116") (pinfunction "P$116_P$116") (pintype "bidirectional"))
    )
    (net (code "301") (name "unconnected-(U$3-PadP$117)") (class "Default")
      (node (ref "U$3") (pin "P$117") (pinfunction "P$117_P$117") (pintype "bidirectional"))
    )
    (net (code "302") (name "unconnected-(U$3-PadP$119)") (class "Default")
      (node (ref "U$3") (pin "P$119") (pinfunction "P$119_P$119") (pintype "bidirectional"))
    )
    (net (code "303") (name "unconnected-(U$3-PadP$120)") (class "Default")
      (node (ref "U$3") (pin "P$120") (pinfunction "P$120_P$120") (pintype "bidirectional"))
    )
    (net (code "304") (name "unconnected-(U$3-SD-CLK-PadP$106)") (class "Default")
      (node (ref "U$3") (pin "P$106") (pinfunction "SD-CLK_P$106") (pintype "bidirectional"))
    )
    (net (code "305") (name "unconnected-(U$3-SD-CMD-PadP$105)") (class "Default")
      (node (ref "U$3") (pin "P$105") (pinfunction "SD-CMD_P$105") (pintype "bidirectional"))
    )
    (net (code "306") (name "unconnected-(U$3-SD-D0-PadP$104)") (class "Default")
      (node (ref "U$3") (pin "P$104") (pinfunction "SD-D0_P$104") (pintype "bidirectional"))
    )
    (net (code "307") (name "unconnected-(U$3-SD-D1-PadP$103)") (class "Default")
      (node (ref "U$3") (pin "P$103") (pinfunction "SD-D1_P$103") (pintype "bidirectional"))
    )
    (net (code "308") (name "unconnected-(U$3-SD-D2-PadP$102)") (class "Default")
      (node (ref "U$3") (pin "P$102") (pinfunction "SD-D2_P$102") (pintype "bidirectional"))
    )
    (net (code "309") (name "unconnected-(U$3-SD-D3-PadP$101)") (class "Default")
      (node (ref "U$3") (pin "P$101") (pinfunction "SD-D3_P$101") (pintype "bidirectional"))
    )
    (net (code "310") (name "unconnected-(U$3-UART5-CTSN-PadP$95)") (class "Default")
      (node (ref "U$3") (pin "P$95") (pinfunction "UART5-CTSN_P$95") (pintype "bidirectional"))
    )
    (net (code "311") (name "unconnected-(U$3-UART5-RTSN-PadP$92)") (class "Default")
      (node (ref "U$3") (pin "P$92") (pinfunction "UART5-RTSN_P$92") (pintype "bidirectional"))
    )
    (net (code "312") (name "unconnected-(U$3-UART5-RX-PadP$94)") (class "Default")
      (node (ref "U$3") (pin "P$94") (pinfunction "UART5-RX_P$94") (pintype "bidirectional"))
    )
    (net (code "313") (name "unconnected-(U$3-UART5-TX-PadP$93)") (class "Default")
      (node (ref "U$3") (pin "P$93") (pinfunction "UART5-TX_P$93") (pintype "bidirectional"))
    )
    (net (code "314") (name "unconnected-(U$3-USB0-ID-PadP$112)") (class "Default")
      (node (ref "U$3") (pin "P$112") (pinfunction "USB0-ID_P$112") (pintype "bidirectional"))
    )
    (net (code "315") (name "unconnected-(U$3-USB0-VBUSDET-PadP$113)") (class "Default")
      (node (ref "U$3") (pin "P$113") (pinfunction "USB0-VBUSDET_P$113") (pintype "bidirectional"))
    )
    (net (code "316") (name "unconnected-(U2-TS-Pad47)") (class "Default")
      (node (ref "U2") (pin "47") (pinfunction "TS_47") (pintype "input"))
    )
  )
)
